# ROHM_102022.net
KiCad netlist of a schematic drawn in EAGLE
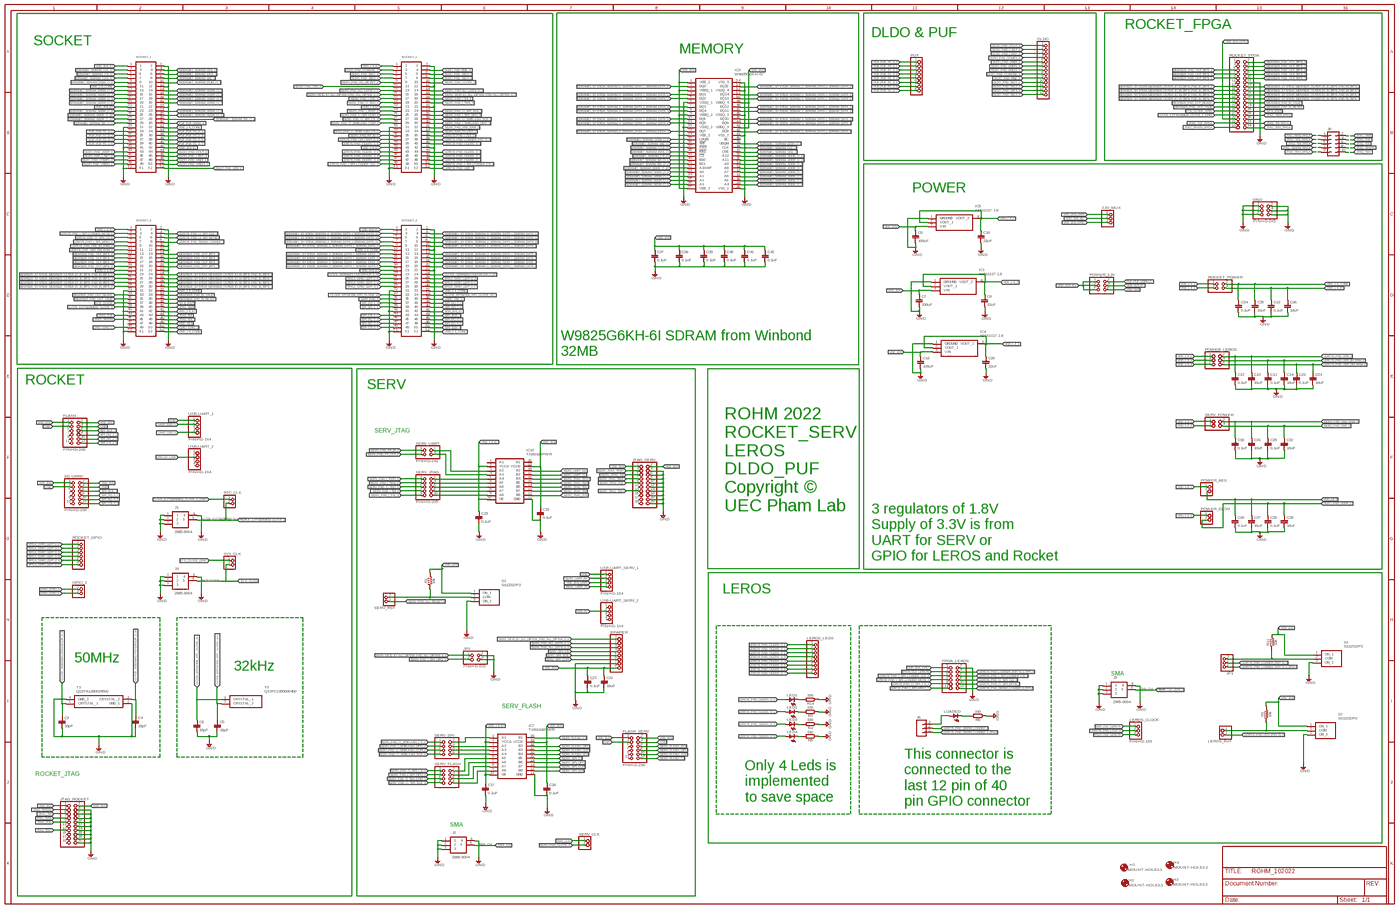
[diagram p0: schematic, sheet 1, overview]
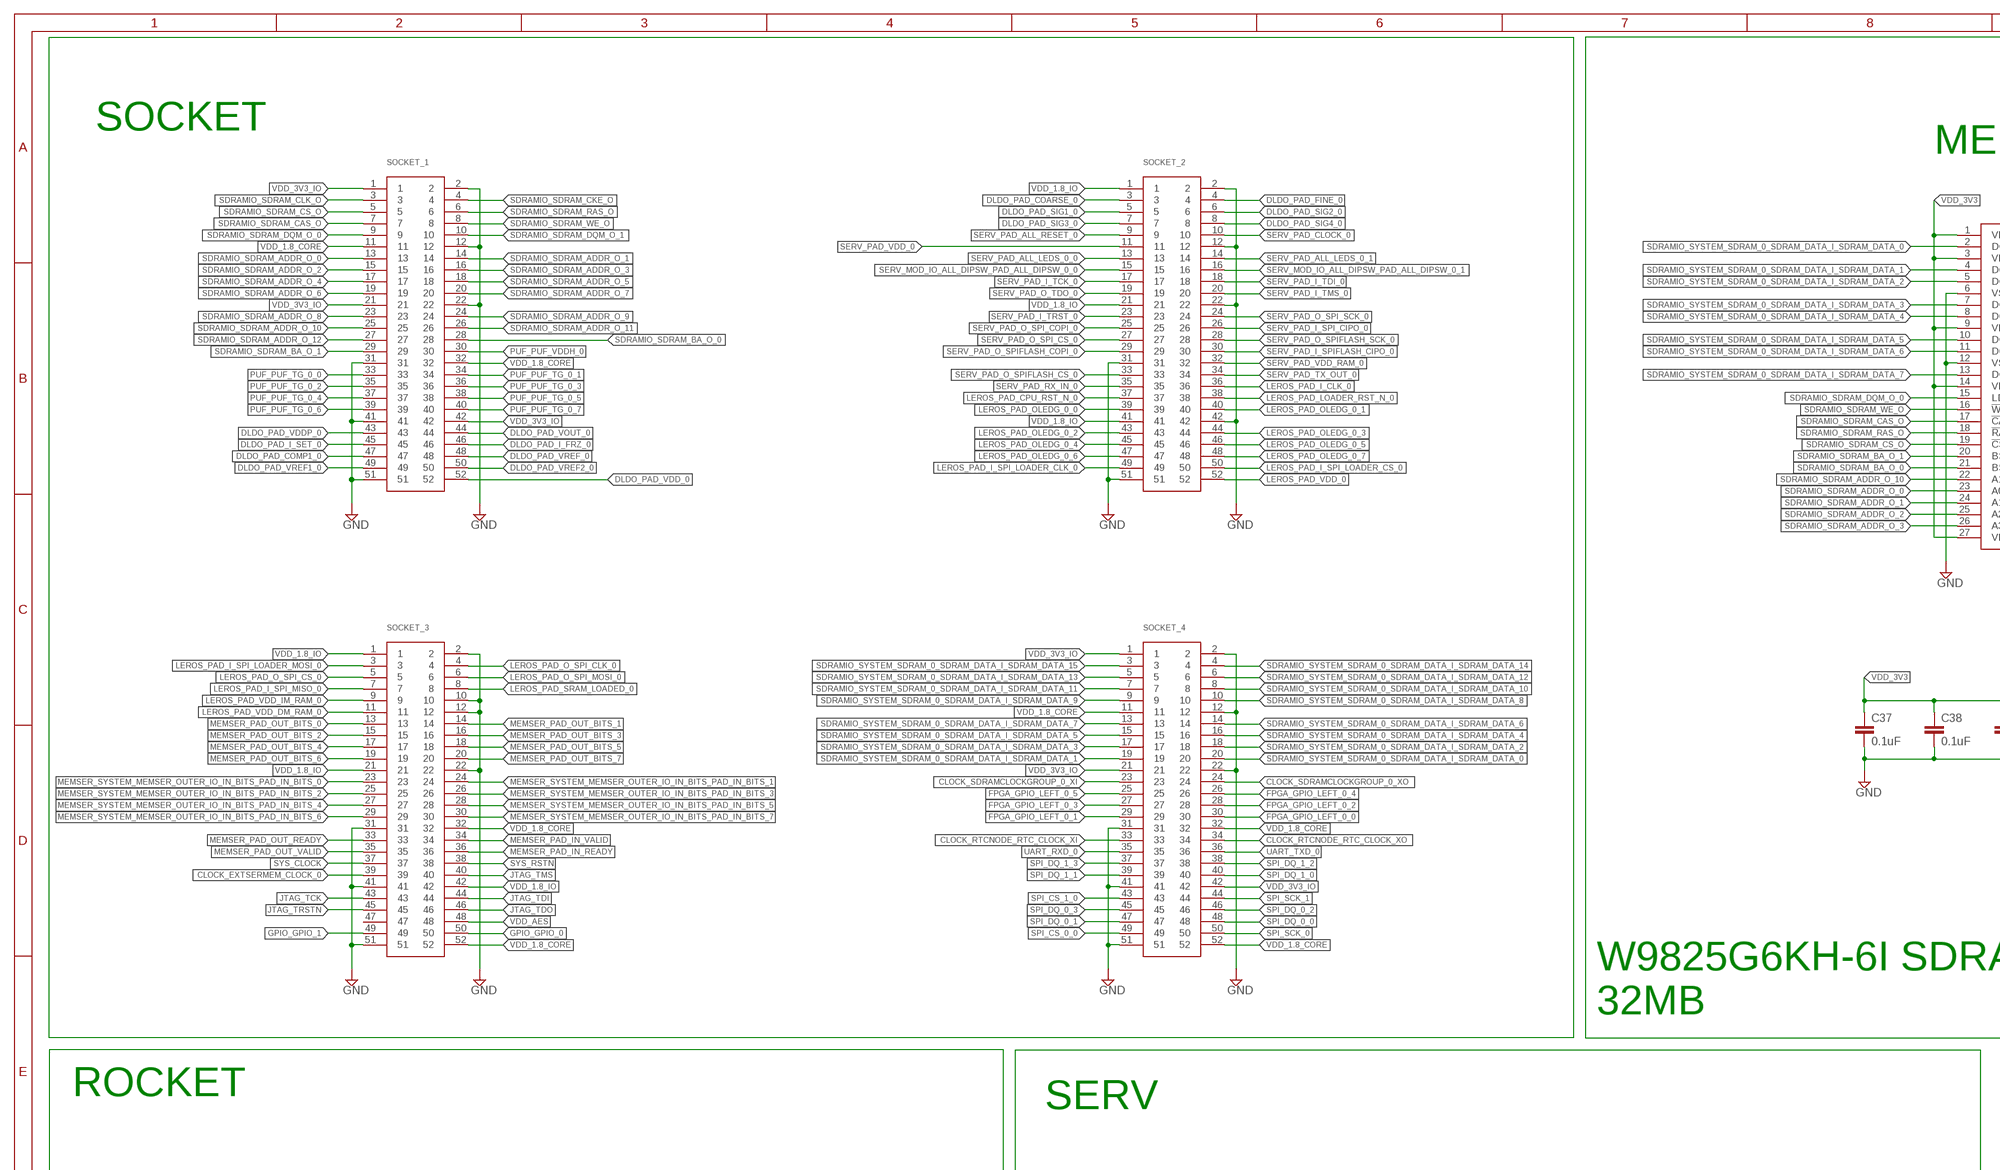
[diagram p1: schematic, sheet 1, part 1 of 4]
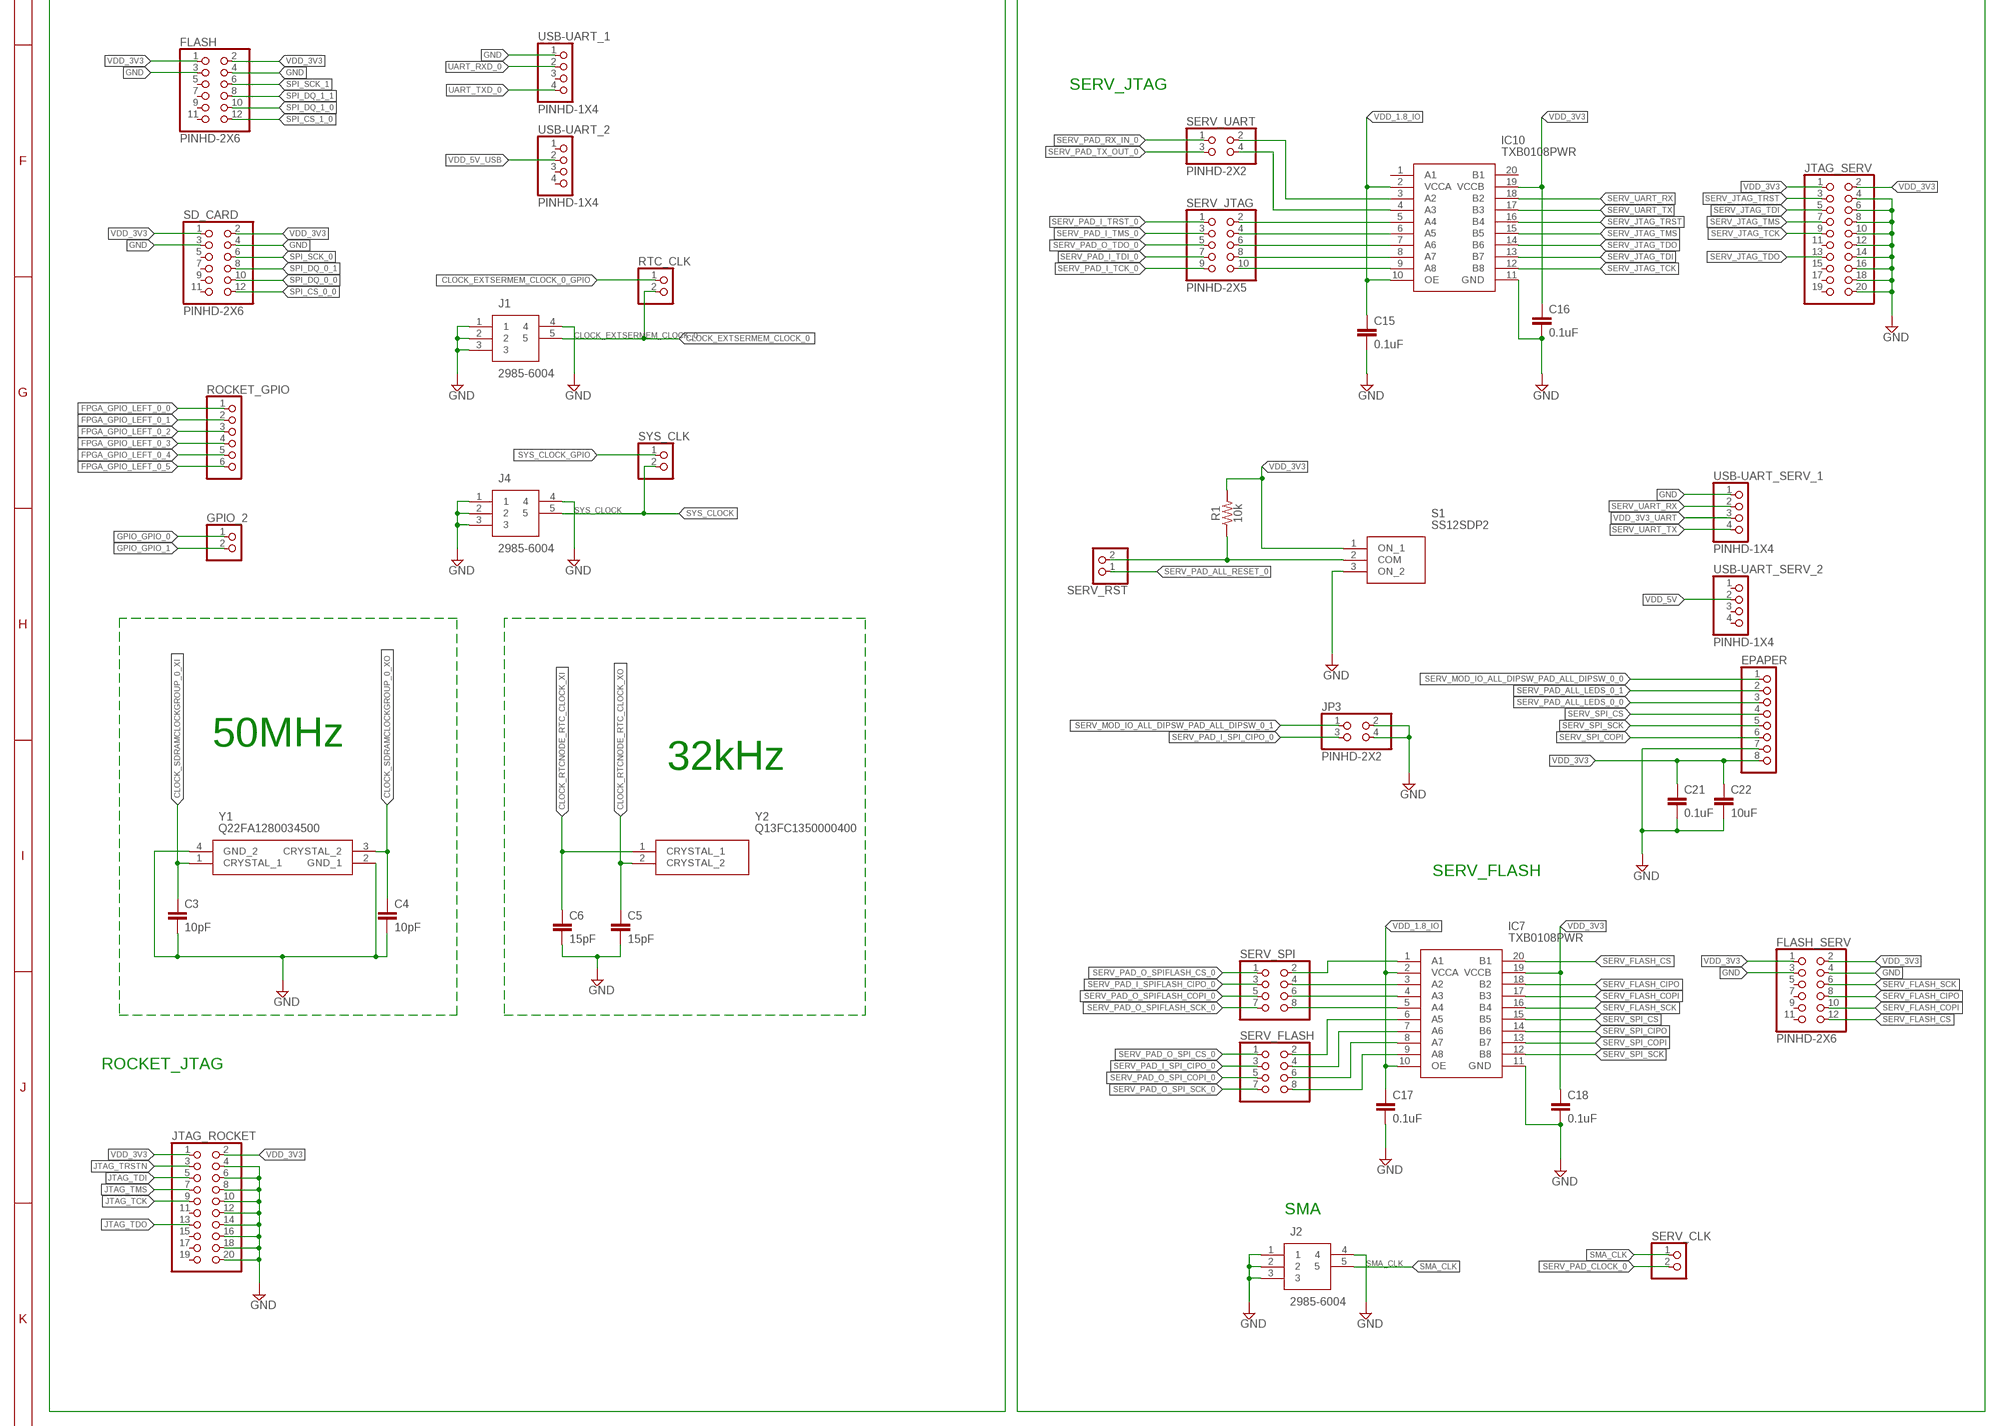
[diagram p2: schematic, sheet 1, part 2 of 4]
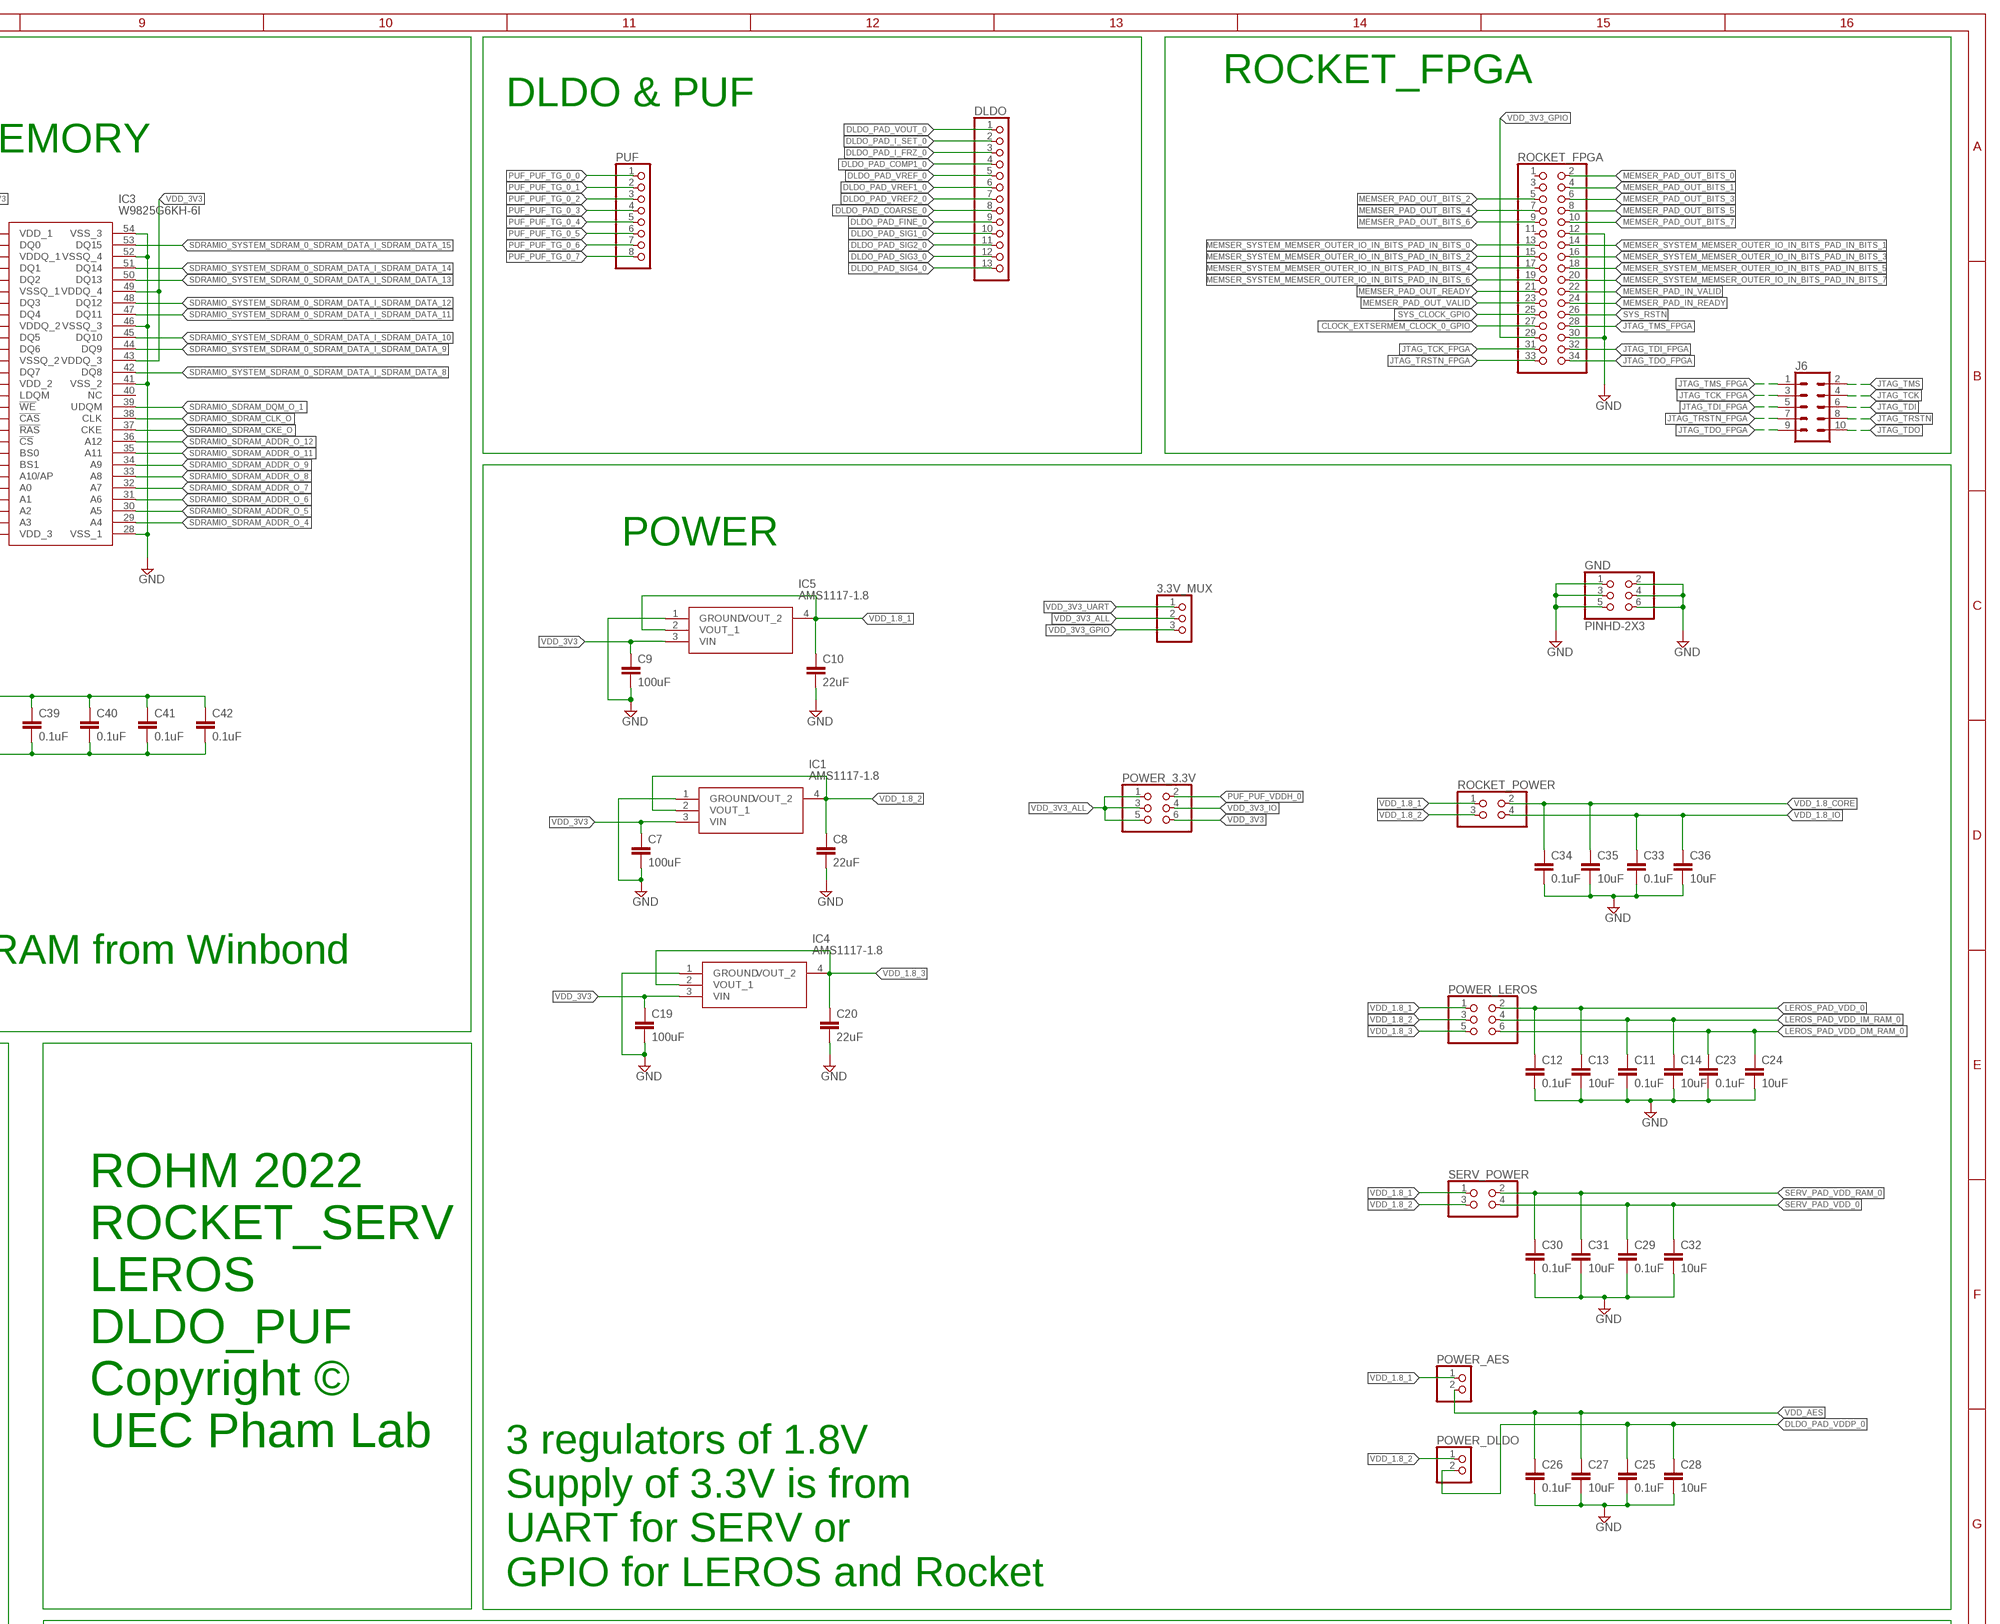
[diagram p3: schematic, sheet 1, part 3 of 4]
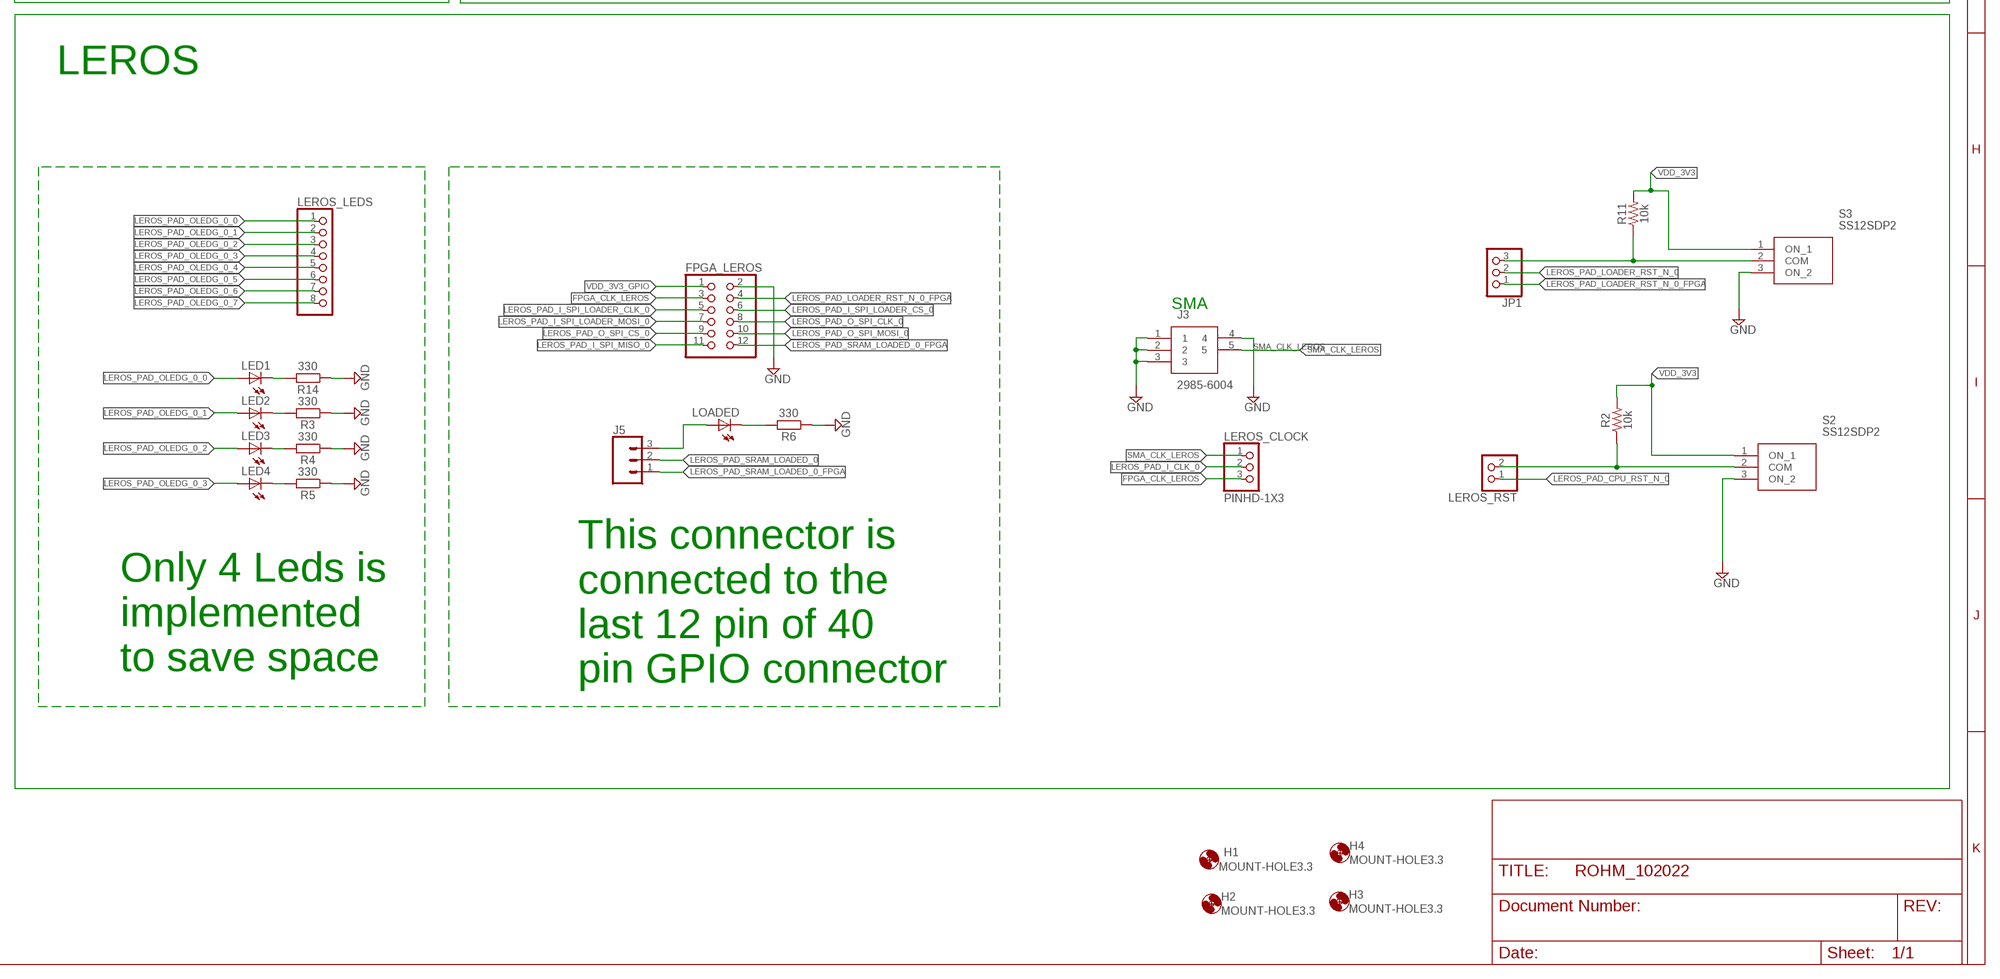
[diagram p4: schematic, sheet 1, part 4 of 4]

(export (version "E")
  (design (tool "Eeschema 10.0.6"))
  (components
    (comp (ref "3.3V_MUX")
      (value "PINHD-1X3")
      (footprint "eagle-import:1X03")
      (libsource (lib "eagle-import") (part "pinhead_325_PINHD-1X3"))
    )
    (comp (ref "C3")
      (value "10pF")
      (footprint "eagle-import:1206")
      (libsource (lib "eagle-import") (part "1.0UF-1206-50V-10%"))
    )
    (comp (ref "C4")
      (value "10pF")
      (footprint "eagle-import:1206")
      (libsource (lib "eagle-import") (part "1.0UF-1206-50V-10%"))
    )
    (comp (ref "C5")
      (value "15pF")
      (footprint "eagle-import:1206")
      (libsource (lib "eagle-import") (part "1.0UF-1206-50V-10%"))
    )
    (comp (ref "C6")
      (value "15pF")
      (footprint "eagle-import:1206")
      (libsource (lib "eagle-import") (part "1.0UF-1206-50V-10%"))
    )
    (comp (ref "C7")
      (value "100uF")
      (footprint "eagle-import:1206")
      (libsource (lib "eagle-import") (part "1.0UF-1206-50V-10%"))
    )
    (comp (ref "C8")
      (value "22uF")
      (footprint "eagle-import:1206")
      (libsource (lib "eagle-import") (part "1.0UF-1206-50V-10%"))
    )
    (comp (ref "C9")
      (value "100uF")
      (footprint "eagle-import:1206")
      (libsource (lib "eagle-import") (part "1.0UF-1206-50V-10%"))
    )
    (comp (ref "C10")
      (value "22uF")
      (footprint "eagle-import:1206")
      (libsource (lib "eagle-import") (part "1.0UF-1206-50V-10%"))
    )
    (comp (ref "C11")
      (value "0.1uF")
      (footprint "eagle-import:1206")
      (libsource (lib "eagle-import") (part "1.0UF-1206-50V-10%"))
    )
    (comp (ref "C12")
      (value "0.1uF")
      (footprint "eagle-import:1206")
      (libsource (lib "eagle-import") (part "1.0UF-1206-50V-10%"))
    )
    (comp (ref "C13")
      (value "10uF")
      (footprint "eagle-import:1206")
      (libsource (lib "eagle-import") (part "1.0UF-1206-50V-10%"))
    )
    (comp (ref "C14")
      (value "10uF")
      (footprint "eagle-import:1206")
      (libsource (lib "eagle-import") (part "1.0UF-1206-50V-10%"))
    )
    (comp (ref "C15")
      (value "0.1uF")
      (footprint "eagle-import:1206")
      (libsource (lib "eagle-import") (part "10UF-1206-6.3V-20%"))
    )
    (comp (ref "C16")
      (value "0.1uF")
      (footprint "eagle-import:1206")
      (libsource (lib "eagle-import") (part "10UF-1206-6.3V-20%"))
    )
    (comp (ref "C17")
      (value "0.1uF")
      (footprint "eagle-import:1206")
      (libsource (lib "eagle-import") (part "10UF-1206-6.3V-20%"))
    )
    (comp (ref "C18")
      (value "0.1uF")
      (footprint "eagle-import:1206")
      (libsource (lib "eagle-import") (part "10UF-1206-6.3V-20%"))
    )
    (comp (ref "C19")
      (value "100uF")
      (footprint "eagle-import:1206")
      (libsource (lib "eagle-import") (part "1.0UF-1206-50V-10%"))
    )
    (comp (ref "C20")
      (value "22uF")
      (footprint "eagle-import:1206")
      (libsource (lib "eagle-import") (part "1.0UF-1206-50V-10%"))
    )
    (comp (ref "C21")
      (value "0.1uF")
      (footprint "eagle-import:1206")
      (libsource (lib "eagle-import") (part "10UF-1206-6.3V-20%"))
    )
    (comp (ref "C22")
      (value "10uF")
      (footprint "eagle-import:1206")
      (libsource (lib "eagle-import") (part "10UF-1206-6.3V-20%"))
    )
    (comp (ref "C23")
      (value "0.1uF")
      (footprint "eagle-import:1206")
      (libsource (lib "eagle-import") (part "1.0UF-1206-50V-10%"))
    )
    (comp (ref "C24")
      (value "10uF")
      (footprint "eagle-import:1206")
      (libsource (lib "eagle-import") (part "1.0UF-1206-50V-10%"))
    )
    (comp (ref "C25")
      (value "0.1uF")
      (footprint "eagle-import:1206")
      (libsource (lib "eagle-import") (part "1.0UF-1206-50V-10%"))
    )
    (comp (ref "C26")
      (value "0.1uF")
      (footprint "eagle-import:1206")
      (libsource (lib "eagle-import") (part "1.0UF-1206-50V-10%"))
    )
    (comp (ref "C27")
      (value "10uF")
      (footprint "eagle-import:1206")
      (libsource (lib "eagle-import") (part "1.0UF-1206-50V-10%"))
    )
    (comp (ref "C28")
      (value "10uF")
      (footprint "eagle-import:1206")
      (libsource (lib "eagle-import") (part "1.0UF-1206-50V-10%"))
    )
    (comp (ref "C29")
      (value "0.1uF")
      (footprint "eagle-import:1206")
      (libsource (lib "eagle-import") (part "1.0UF-1206-50V-10%"))
    )
    (comp (ref "C30")
      (value "0.1uF")
      (footprint "eagle-import:1206")
      (libsource (lib "eagle-import") (part "1.0UF-1206-50V-10%"))
    )
    (comp (ref "C31")
      (value "10uF")
      (footprint "eagle-import:1206")
      (libsource (lib "eagle-import") (part "1.0UF-1206-50V-10%"))
    )
    (comp (ref "C32")
      (value "10uF")
      (footprint "eagle-import:1206")
      (libsource (lib "eagle-import") (part "1.0UF-1206-50V-10%"))
    )
    (comp (ref "C33")
      (value "0.1uF")
      (footprint "eagle-import:1206")
      (libsource (lib "eagle-import") (part "1.0UF-1206-50V-10%"))
    )
    (comp (ref "C34")
      (value "0.1uF")
      (footprint "eagle-import:1206")
      (libsource (lib "eagle-import") (part "1.0UF-1206-50V-10%"))
    )
    (comp (ref "C35")
      (value "10uF")
      (footprint "eagle-import:1206")
      (libsource (lib "eagle-import") (part "1.0UF-1206-50V-10%"))
    )
    (comp (ref "C36")
      (value "10uF")
      (footprint "eagle-import:1206")
      (libsource (lib "eagle-import") (part "1.0UF-1206-50V-10%"))
    )
    (comp (ref "C37")
      (value "0.1uF")
      (footprint "eagle-import:1206")
      (libsource (lib "eagle-import") (part "10UF-1206-6.3V-20%"))
    )
    (comp (ref "C38")
      (value "0.1uF")
      (footprint "eagle-import:1206")
      (libsource (lib "eagle-import") (part "10UF-1206-6.3V-20%"))
    )
    (comp (ref "C39")
      (value "0.1uF")
      (footprint "eagle-import:1206")
      (libsource (lib "eagle-import") (part "10UF-1206-6.3V-20%"))
    )
    (comp (ref "C40")
      (value "0.1uF")
      (footprint "eagle-import:1206")
      (libsource (lib "eagle-import") (part "10UF-1206-6.3V-20%"))
    )
    (comp (ref "C41")
      (value "0.1uF")
      (footprint "eagle-import:1206")
      (libsource (lib "eagle-import") (part "10UF-1206-6.3V-20%"))
    )
    (comp (ref "C42")
      (value "0.1uF")
      (footprint "eagle-import:1206")
      (libsource (lib "eagle-import") (part "10UF-1206-6.3V-20%"))
    )
    (comp (ref "DLDO")
      (value "PINHD-1X13")
      (footprint "eagle-import:1X13")
      (libsource (lib "eagle-import") (part "PINHD-1X13"))
    )
    (comp (ref "EPAPER")
      (value "PINHD-1X8")
      (footprint "eagle-import:1X08")
      (libsource (lib "eagle-import") (part "PINHD-1X8"))
    )
    (comp (ref "FLASH")
      (value "PINHD-2X6")
      (footprint "eagle-import:2X06")
      (libsource (lib "eagle-import") (part "PINHD-2X6"))
    )
    (comp (ref "FLASH_SERV")
      (value "PINHD-2X6")
      (footprint "eagle-import:2X06")
      (libsource (lib "eagle-import") (part "PINHD-2X6"))
    )
    (comp (ref "FPGA_LEROS")
      (value "PINHD-2X6")
      (footprint "eagle-import:2X06")
      (libsource (lib "eagle-import") (part "pinhead_325_PINHD-2X6"))
    )
    (comp (ref "GND")
      (value "PINHD-2X3")
      (footprint "eagle-import:2X03")
      (libsource (lib "eagle-import") (part "PINHD-2X3"))
    )
    (comp (ref "GPIO_2")
      (value "PINHD-1X2")
      (footprint "eagle-import:1X02")
      (libsource (lib "eagle-import") (part "PINHD-1X2"))
    )
    (comp (ref "H1")
      (value "MOUNT-HOLE3.3")
      (footprint "eagle-import:3,3")
      (libsource (lib "eagle-import") (part "MOUNT-HOLE3.3"))
    )
    (comp (ref "H2")
      (value "MOUNT-HOLE3.3")
      (footprint "eagle-import:3,3")
      (libsource (lib "eagle-import") (part "MOUNT-HOLE3.3"))
    )
    (comp (ref "H3")
      (value "MOUNT-HOLE3.3")
      (footprint "eagle-import:3,3")
      (libsource (lib "eagle-import") (part "MOUNT-HOLE3.3"))
    )
    (comp (ref "H4")
      (value "MOUNT-HOLE3.3")
      (footprint "eagle-import:3,3")
      (libsource (lib "eagle-import") (part "MOUNT-HOLE3.3"))
    )
    (comp (ref "IC1")
      (value "AMS1117-1.8")
      (footprint "eagle-import:SOT229P700X180-4N")
      (fields (field (name "MANUFACTURER_PART_NUMBER") "AMS1117"))
      (libsource (lib "eagle-import") (part "AMS1117"))
    )
    (comp (ref "IC3")
      (value "W9825G6KH-6I")
      (footprint "eagle-import:SOP80P1176X120-54N")
      (fields (field (name "MOUSER_PART_NUMBER") "454-W9825G6KH-6I"))
      (libsource (lib "eagle-import") (part "W9825G6KH-6I"))
    )
    (comp (ref "IC4")
      (value "AMS1117-1.8")
      (footprint "eagle-import:SOT229P700X180-4N")
      (fields (field (name "MANUFACTURER_PART_NUMBER") "AMS1117"))
      (libsource (lib "eagle-import") (part "AMS1117"))
    )
    (comp (ref "IC5")
      (value "AMS1117-1.8")
      (footprint "eagle-import:SOT229P700X180-4N")
      (fields (field (name "MANUFACTURER_PART_NUMBER") "AMS1117"))
      (libsource (lib "eagle-import") (part "AMS1117"))
    )
    (comp (ref "IC7")
      (value "TXB0108PWR")
      (footprint "eagle-import:SOP65P640X120-20N")
      (fields (field (name "MOUSER_PART_NUMBER") "595-TXB0108PWR"))
      (libsource (lib "eagle-import") (part "TXB0108PWR"))
    )
    (comp (ref "IC10")
      (value "TXB0108PWR")
      (footprint "eagle-import:SOP65P640X120-20N")
      (fields (field (name "MOUSER_PART_NUMBER") "595-TXB0108PWR"))
      (libsource (lib "eagle-import") (part "TXB0108PWR"))
    )
    (comp (ref "J1")
      (value "2985-6004")
      (footprint "eagle-import:29856004")
      (fields (field (name "MOUSER_PART_NUMBER") "523-2985-6004"))
      (libsource (lib "eagle-import") (part "2985-6004"))
    )
    (comp (ref "J2")
      (value "2985-6004")
      (footprint "eagle-import:29856004")
      (fields (field (name "MOUSER_PART_NUMBER") "523-2985-6004"))
      (libsource (lib "eagle-import") (part "2985-6004"))
    )
    (comp (ref "J3")
      (value "2985-6004")
      (footprint "eagle-import:29856004")
      (fields (field (name "MOUSER_PART_NUMBER") "523-2985-6004"))
      (libsource (lib "eagle-import") (part "2985-6004"))
    )
    (comp (ref "J4")
      (value "2985-6004")
      (footprint "eagle-import:29856004")
      (fields (field (name "MOUSER_PART_NUMBER") "523-2985-6004"))
      (libsource (lib "eagle-import") (part "2985-6004"))
    )
    (comp (ref "J5")
      (value "CONN_03")
      (footprint "eagle-import:1X03")
      (libsource (lib "eagle-import") (part "CONN_03"))
    )
    (comp (ref "J6")
      (value "CONN_05X2PTH")
      (footprint "eagle-import:2X5")
      (libsource (lib "eagle-import") (part "CONN_05X2PTH"))
    )
    (comp (ref "JP1")
      (value "PINHD-1X3")
      (footprint "eagle-import:1X03")
      (libsource (lib "eagle-import") (part "pinhead_325_PINHD-1X3"))
    )
    (comp (ref "JP3")
      (value "PINHD-2X2")
      (footprint "eagle-import:2X02")
      (libsource (lib "eagle-import") (part "PINHD-2X2"))
    )
    (comp (ref "JTAG_ROCKET")
      (value "PINHD-2X10")
      (footprint "eagle-import:2X10")
      (libsource (lib "eagle-import") (part "PINHD-2X10"))
    )
    (comp (ref "JTAG_SERV")
      (value "PINHD-2X10")
      (footprint "eagle-import:2X10")
      (libsource (lib "eagle-import") (part "PINHD-2X10"))
    )
    (comp (ref "LED1")
      (value "LEDCHIPLED_0805")
      (footprint "eagle-import:CHIPLED_0805")
      (libsource (lib "eagle-import") (part "LEDCHIPLED_0805"))
    )
    (comp (ref "LED2")
      (value "LEDCHIPLED_0805")
      (footprint "eagle-import:CHIPLED_0805")
      (libsource (lib "eagle-import") (part "LEDCHIPLED_0805"))
    )
    (comp (ref "LED3")
      (value "LEDCHIPLED_0805")
      (footprint "eagle-import:CHIPLED_0805")
      (libsource (lib "eagle-import") (part "LEDCHIPLED_0805"))
    )
    (comp (ref "LED4")
      (value "LEDCHIPLED_0805")
      (footprint "eagle-import:CHIPLED_0805")
      (libsource (lib "eagle-import") (part "LEDCHIPLED_0805"))
    )
    (comp (ref "LEROS_CLOCK")
      (value "PINHD-1X3")
      (footprint "eagle-import:1X03")
      (libsource (lib "eagle-import") (part "PINHD-1X3"))
    )
    (comp (ref "LEROS_LEDS")
      (value "PINHD-1X8")
      (footprint "eagle-import:1X08")
      (libsource (lib "eagle-import") (part "PINHD-1X8"))
    )
    (comp (ref "LEROS_RST")
      (value "PINHD-1X2")
      (footprint "eagle-import:1X02")
      (libsource (lib "eagle-import") (part "PINHD-1X2"))
    )
    (comp (ref "LOADED")
      (value "LEDCHIPLED_0805")
      (footprint "eagle-import:CHIPLED_0805")
      (libsource (lib "eagle-import") (part "LEDCHIPLED_0805"))
    )
    (comp (ref "POWER_3.3V")
      (value "PINHD-2X3")
      (footprint "eagle-import:2X03")
      (libsource (lib "eagle-import") (part "pinhead_325_PINHD-2X3"))
    )
    (comp (ref "POWER_AES")
      (value "PINHD-1X2")
      (footprint "eagle-import:1X02")
      (libsource (lib "eagle-import") (part "PINHD-1X2"))
    )
    (comp (ref "POWER_DLDO")
      (value "PINHD-1X2")
      (footprint "eagle-import:1X02")
      (libsource (lib "eagle-import") (part "PINHD-1X2"))
    )
    (comp (ref "POWER_LEROS")
      (value "PINHD-2X3")
      (footprint "eagle-import:2X03")
      (libsource (lib "eagle-import") (part "pinhead_325_PINHD-2X3"))
    )
    (comp (ref "PUF")
      (value "PINHD-1X8")
      (footprint "eagle-import:1X08")
      (libsource (lib "eagle-import") (part "PINHD-1X8"))
    )
    (comp (ref "R1")
      (value "10k")
      (footprint "eagle-import:1206")
      (libsource (lib "eagle-import") (part "10OHM-1206-1/4W-1%"))
    )
    (comp (ref "R2")
      (value "10k")
      (footprint "eagle-import:1206")
      (libsource (lib "eagle-import") (part "10OHM-1206-1/4W-1%"))
    )
    (comp (ref "R3")
      (value "330")
      (footprint "eagle-import:RESC3216X70")
      (libsource (lib "eagle-import") (part "RCHIP-1206(3216-METRIC)_"))
    )
    (comp (ref "R4")
      (value "330")
      (footprint "eagle-import:RESC3216X70")
      (libsource (lib "eagle-import") (part "RCHIP-1206(3216-METRIC)_"))
    )
    (comp (ref "R5")
      (value "330")
      (footprint "eagle-import:RESC3216X70")
      (libsource (lib "eagle-import") (part "RCHIP-1206(3216-METRIC)_"))
    )
    (comp (ref "R6")
      (value "330")
      (footprint "eagle-import:RESC3216X70")
      (libsource (lib "eagle-import") (part "RCHIP-1206(3216-METRIC)_"))
    )
    (comp (ref "R11")
      (value "10k")
      (footprint "eagle-import:1206")
      (libsource (lib "eagle-import") (part "10OHM-1206-1/4W-1%"))
    )
    (comp (ref "R14")
      (value "330")
      (footprint "eagle-import:RESC3216X70")
      (libsource (lib "eagle-import") (part "RCHIP-1206(3216-METRIC)_"))
    )
    (comp (ref "ROCKET_FPGA")
      (value "PINHD-2X17")
      (footprint "eagle-import:2X17")
      (libsource (lib "eagle-import") (part "PINHD-2X17"))
    )
    (comp (ref "ROCKET_GPIO")
      (value "PINHD-1X6")
      (footprint "eagle-import:1X06")
      (libsource (lib "eagle-import") (part "PINHD-1X6"))
    )
    (comp (ref "ROCKET_POWER")
      (value "PINHD-2X2")
      (footprint "eagle-import:2X02")
      (libsource (lib "eagle-import") (part "pinhead_325_PINHD-2X2"))
    )
    (comp (ref "RTC_CLK")
      (value "PINHD-1X2")
      (footprint "eagle-import:1X02")
      (libsource (lib "eagle-import") (part "PINHD-1X2"))
    )
    (comp (ref "S1")
      (value "SS12SDP2")
      (footprint "eagle-import:SS12SDP2")
      (fields (field (name "MOUSER_PART_NUMBER") "633-SS12SDP2"))
      (libsource (lib "eagle-import") (part "SS12SDP2"))
    )
    (comp (ref "S2")
      (value "SS12SDP2")
      (footprint "eagle-import:SS12SDP2")
      (fields (field (name "MOUSER_PART_NUMBER") "633-SS12SDP2"))
      (libsource (lib "eagle-import") (part "SS12SDP2"))
    )
    (comp (ref "S3")
      (value "SS12SDP2")
      (footprint "eagle-import:SS12SDP2")
      (fields (field (name "MOUSER_PART_NUMBER") "633-SS12SDP2"))
      (libsource (lib "eagle-import") (part "SS12SDP2"))
    )
    (comp (ref "SD_CARD")
      (value "PINHD-2X6")
      (footprint "eagle-import:2X06")
      (libsource (lib "eagle-import") (part "PINHD-2X6"))
    )
    (comp (ref "SERV_CLK")
      (value "PINHD-1X2")
      (footprint "eagle-import:1X02")
      (libsource (lib "eagle-import") (part "PINHD-1X2"))
    )
    (comp (ref "SERV_FLASH")
      (value "PINHD-2X4")
      (footprint "eagle-import:2X04")
      (libsource (lib "eagle-import") (part "PINHD-2X4"))
    )
    (comp (ref "SERV_JTAG")
      (value "PINHD-2X5")
      (footprint "eagle-import:2X05")
      (libsource (lib "eagle-import") (part "PINHD-2X5"))
    )
    (comp (ref "SERV_POWER")
      (value "PINHD-2X2")
      (footprint "eagle-import:2X02")
      (libsource (lib "eagle-import") (part "pinhead_325_PINHD-2X2"))
    )
    (comp (ref "SERV_RST")
      (value "PINHD-1X2")
      (footprint "eagle-import:1X02")
      (libsource (lib "eagle-import") (part "PINHD-1X2"))
    )
    (comp (ref "SERV_SPI")
      (value "PINHD-2X4")
      (footprint "eagle-import:2X04")
      (libsource (lib "eagle-import") (part "PINHD-2X4"))
    )
    (comp (ref "SERV_UART")
      (value "PINHD-2X2")
      (footprint "eagle-import:2X02")
      (libsource (lib "eagle-import") (part "PINHD-2X2"))
    )
    (comp (ref "SOCKET_1")
      (value "2X26_HEADER")
      (footprint "eagle-import:2X26_HEADER")
      (libsource (lib "eagle-import") (part "2X26_HEADER"))
    )
    (comp (ref "SOCKET_2")
      (value "2X26_HEADER")
      (footprint "eagle-import:2X26_HEADER")
      (libsource (lib "eagle-import") (part "2X26_HEADER"))
    )
    (comp (ref "SOCKET_3")
      (value "2X26_HEADER")
      (footprint "eagle-import:2X26_HEADER")
      (libsource (lib "eagle-import") (part "2X26_HEADER"))
    )
    (comp (ref "SOCKET_4")
      (value "2X26_HEADER")
      (footprint "eagle-import:2X26_HEADER")
      (libsource (lib "eagle-import") (part "2X26_HEADER"))
    )
    (comp (ref "SYS_CLK")
      (value "PINHD-1X2")
      (footprint "eagle-import:1X02")
      (libsource (lib "eagle-import") (part "PINHD-1X2"))
    )
    (comp (ref "USB-UART_1")
      (value "PINHD-1X4")
      (footprint "eagle-import:1X04")
      (libsource (lib "eagle-import") (part "PINHD-1X4"))
    )
    (comp (ref "USB-UART_2")
      (value "PINHD-1X4")
      (footprint "eagle-import:1X04")
      (libsource (lib "eagle-import") (part "PINHD-1X4"))
    )
    (comp (ref "USB-UART_SERV_1")
      (value "PINHD-1X4")
      (footprint "eagle-import:1X04")
      (libsource (lib "eagle-import") (part "PINHD-1X4"))
    )
    (comp (ref "USB-UART_SERV_2")
      (value "PINHD-1X4")
      (footprint "eagle-import:1X04")
      (libsource (lib "eagle-import") (part "PINHD-1X4"))
    )
    (comp (ref "Y1")
      (value "Q22FA1280034500")
      (footprint "eagle-import:Q22FA1280034500")
      (libsource (lib "eagle-import") (part "Q22FA1280034500"))
    )
    (comp (ref "Y2")
      (value "Q13FC1350000400")
      (footprint "eagle-import:Q13FC1350000400")
      (libsource (lib "eagle-import") (part "Q13FC1350000400"))
    )
  )
  (nets
    (net (code "1") (name "CLOCK_EXTSERMEM_CLOCK_0") (class "Default")
      (node (ref "J1") (pin "5") (pinfunction "5_5") (pintype "bidirectional"))
      (node (ref "RTC_CLK") (pin "2") (pinfunction "2_2") (pintype "passive"))
      (node (ref "SOCKET_3") (pin "39") (pinfunction "39_39") (pintype "bidirectional"))
    )
    (net (code "2") (name "CLOCK_EXTSERMEM_CLOCK_0_GPIO") (class "Default")
      (node (ref "ROCKET_FPGA") (pin "27") (pinfunction "27_27") (pintype "passive"))
      (node (ref "RTC_CLK") (pin "1") (pinfunction "1_1") (pintype "passive"))
    )
    (net (code "3") (name "CLOCK_RTCNODE_RTC_CLOCK_XI") (class "Default")
      (node (ref "C6") (pin "1") (pinfunction "1_1") (pintype "passive"))
      (node (ref "SOCKET_4") (pin "33") (pinfunction "33_33") (pintype "bidirectional"))
      (node (ref "Y2") (pin "1") (pinfunction "CRYSTAL_1_1") (pintype "bidirectional"))
    )
    (net (code "4") (name "CLOCK_RTCNODE_RTC_CLOCK_XO") (class "Default")
      (node (ref "C5") (pin "1") (pinfunction "1_1") (pintype "passive"))
      (node (ref "SOCKET_4") (pin "34") (pinfunction "34_34") (pintype "bidirectional"))
      (node (ref "Y2") (pin "2") (pinfunction "CRYSTAL_2_2") (pintype "bidirectional"))
    )
    (net (code "5") (name "CLOCK_SDRAMCLOCKGROUP_0_XI") (class "Default")
      (node (ref "C3") (pin "1") (pinfunction "1_1") (pintype "passive"))
      (node (ref "SOCKET_4") (pin "23") (pinfunction "23_23") (pintype "bidirectional"))
      (node (ref "Y1") (pin "1") (pinfunction "CRYSTAL_1_1") (pintype "bidirectional"))
    )
    (net (code "6") (name "CLOCK_SDRAMCLOCKGROUP_0_XO") (class "Default")
      (node (ref "C4") (pin "1") (pinfunction "1_1") (pintype "passive"))
      (node (ref "SOCKET_4") (pin "24") (pinfunction "24_24") (pintype "bidirectional"))
      (node (ref "Y1") (pin "3") (pinfunction "CRYSTAL_2_3") (pintype "bidirectional"))
    )
    (net (code "7") (name "DLDO_PAD_COARSE_0") (class "Default")
      (node (ref "DLDO") (pin "8") (pinfunction "8_8") (pintype "passive"))
      (node (ref "SOCKET_2") (pin "3") (pinfunction "3_3") (pintype "bidirectional"))
    )
    (net (code "8") (name "DLDO_PAD_COMP1_0") (class "Default")
      (node (ref "DLDO") (pin "4") (pinfunction "4_4") (pintype "passive"))
      (node (ref "SOCKET_1") (pin "47") (pinfunction "47_47") (pintype "bidirectional"))
    )
    (net (code "9") (name "DLDO_PAD_FINE_0") (class "Default")
      (node (ref "DLDO") (pin "9") (pinfunction "9_9") (pintype "passive"))
      (node (ref "SOCKET_2") (pin "4") (pinfunction "4_4") (pintype "bidirectional"))
    )
    (net (code "10") (name "DLDO_PAD_I_FRZ_0") (class "Default")
      (node (ref "DLDO") (pin "3") (pinfunction "3_3") (pintype "passive"))
      (node (ref "SOCKET_1") (pin "46") (pinfunction "46_46") (pintype "bidirectional"))
    )
    (net (code "11") (name "DLDO_PAD_I_SET_0") (class "Default")
      (node (ref "DLDO") (pin "2") (pinfunction "2_2") (pintype "passive"))
      (node (ref "SOCKET_1") (pin "45") (pinfunction "45_45") (pintype "bidirectional"))
    )
    (net (code "12") (name "DLDO_PAD_SIG1_0") (class "Default")
      (node (ref "DLDO") (pin "10") (pinfunction "10_10") (pintype "passive"))
      (node (ref "SOCKET_2") (pin "5") (pinfunction "5_5") (pintype "bidirectional"))
    )
    (net (code "13") (name "DLDO_PAD_SIG2_0") (class "Default")
      (node (ref "DLDO") (pin "11") (pinfunction "11_11") (pintype "passive"))
      (node (ref "SOCKET_2") (pin "6") (pinfunction "6_6") (pintype "bidirectional"))
    )
    (net (code "14") (name "DLDO_PAD_SIG3_0") (class "Default")
      (node (ref "DLDO") (pin "12") (pinfunction "12_12") (pintype "passive"))
      (node (ref "SOCKET_2") (pin "7") (pinfunction "7_7") (pintype "bidirectional"))
    )
    (net (code "15") (name "DLDO_PAD_SIG4_0") (class "Default")
      (node (ref "DLDO") (pin "13") (pinfunction "13_13") (pintype "passive"))
      (node (ref "SOCKET_2") (pin "8") (pinfunction "8_8") (pintype "bidirectional"))
    )
    (net (code "16") (name "DLDO_PAD_VDDP_0") (class "Default")
      (node (ref "C25") (pin "1") (pinfunction "1_1") (pintype "passive"))
      (node (ref "C28") (pin "1") (pinfunction "1_1") (pintype "passive"))
      (node (ref "POWER_DLDO") (pin "2") (pinfunction "2_2") (pintype "passive"))
      (node (ref "SOCKET_1") (pin "43") (pinfunction "43_43") (pintype "bidirectional"))
    )
    (net (code "17") (name "DLDO_PAD_VDD_0") (class "Default")
      (node (ref "SOCKET_1") (pin "52") (pinfunction "52_52") (pintype "bidirectional"))
    )
    (net (code "18") (name "DLDO_PAD_VOUT_0") (class "Default")
      (node (ref "DLDO") (pin "1") (pinfunction "1_1") (pintype "passive"))
      (node (ref "SOCKET_1") (pin "44") (pinfunction "44_44") (pintype "bidirectional"))
    )
    (net (code "19") (name "DLDO_PAD_VREF1_0") (class "Default")
      (node (ref "DLDO") (pin "6") (pinfunction "6_6") (pintype "passive"))
      (node (ref "SOCKET_1") (pin "49") (pinfunction "49_49") (pintype "bidirectional"))
    )
    (net (code "20") (name "DLDO_PAD_VREF2_0") (class "Default")
      (node (ref "DLDO") (pin "7") (pinfunction "7_7") (pintype "passive"))
      (node (ref "SOCKET_1") (pin "50") (pinfunction "50_50") (pintype "bidirectional"))
    )
    (net (code "21") (name "DLDO_PAD_VREF_0") (class "Default")
      (node (ref "DLDO") (pin "5") (pinfunction "5_5") (pintype "passive"))
      (node (ref "SOCKET_1") (pin "48") (pinfunction "48_48") (pintype "bidirectional"))
    )
    (net (code "22") (name "FPGA_CLK_LEROS") (class "Default")
      (node (ref "FPGA_LEROS") (pin "3") (pinfunction "3_3") (pintype "passive"))
      (node (ref "LEROS_CLOCK") (pin "3") (pinfunction "3_3") (pintype "passive"))
    )
    (net (code "23") (name "FPGA_GPIO_LEFT_0_0") (class "Default")
      (node (ref "ROCKET_GPIO") (pin "1") (pinfunction "1_1") (pintype "passive"))
      (node (ref "SOCKET_4") (pin "30") (pinfunction "30_30") (pintype "bidirectional"))
    )
    (net (code "24") (name "FPGA_GPIO_LEFT_0_1") (class "Default")
      (node (ref "ROCKET_GPIO") (pin "2") (pinfunction "2_2") (pintype "passive"))
      (node (ref "SOCKET_4") (pin "29") (pinfunction "29_29") (pintype "bidirectional"))
    )
    (net (code "25") (name "FPGA_GPIO_LEFT_0_2") (class "Default")
      (node (ref "ROCKET_GPIO") (pin "3") (pinfunction "3_3") (pintype "passive"))
      (node (ref "SOCKET_4") (pin "28") (pinfunction "28_28") (pintype "bidirectional"))
    )
    (net (code "26") (name "FPGA_GPIO_LEFT_0_3") (class "Default")
      (node (ref "ROCKET_GPIO") (pin "4") (pinfunction "4_4") (pintype "passive"))
      (node (ref "SOCKET_4") (pin "27") (pinfunction "27_27") (pintype "bidirectional"))
    )
    (net (code "27") (name "FPGA_GPIO_LEFT_0_4") (class "Default")
      (node (ref "ROCKET_GPIO") (pin "5") (pinfunction "5_5") (pintype "passive"))
      (node (ref "SOCKET_4") (pin "26") (pinfunction "26_26") (pintype "bidirectional"))
    )
    (net (code "28") (name "FPGA_GPIO_LEFT_0_5") (class "Default")
      (node (ref "ROCKET_GPIO") (pin "6") (pinfunction "6_6") (pintype "passive"))
      (node (ref "SOCKET_4") (pin "25") (pinfunction "25_25") (pintype "bidirectional"))
    )
    (net (code "29") (name "GND") (class "Default")
      (node (ref "C10") (pin "2") (pinfunction "2_2") (pintype "passive"))
      (node (ref "C11") (pin "2") (pinfunction "2_2") (pintype "passive"))
      (node (ref "C12") (pin "2") (pinfunction "2_2") (pintype "passive"))
      (node (ref "C13") (pin "2") (pinfunction "2_2") (pintype "passive"))
      (node (ref "C14") (pin "2") (pinfunction "2_2") (pintype "passive"))
      (node (ref "C15") (pin "2") (pinfunction "2_2") (pintype "passive"))
      (node (ref "C16") (pin "2") (pinfunction "2_2") (pintype "passive"))
      (node (ref "C17") (pin "2") (pinfunction "2_2") (pintype "passive"))
      (node (ref "C18") (pin "2") (pinfunction "2_2") (pintype "passive"))
      (node (ref "C19") (pin "2") (pinfunction "2_2") (pintype "passive"))
      (node (ref "C20") (pin "2") (pinfunction "2_2") (pintype "passive"))
      (node (ref "C21") (pin "2") (pinfunction "2_2") (pintype "passive"))
      (node (ref "C22") (pin "2") (pinfunction "2_2") (pintype "passive"))
      (node (ref "C23") (pin "2") (pinfunction "2_2") (pintype "passive"))
      (node (ref "C24") (pin "2") (pinfunction "2_2") (pintype "passive"))
      (node (ref "C25") (pin "2") (pinfunction "2_2") (pintype "passive"))
      (node (ref "C26") (pin "2") (pinfunction "2_2") (pintype "passive"))
      (node (ref "C27") (pin "2") (pinfunction "2_2") (pintype "passive"))
      (node (ref "C28") (pin "2") (pinfunction "2_2") (pintype "passive"))
      (node (ref "C29") (pin "2") (pinfunction "2_2") (pintype "passive"))
      (node (ref "C3") (pin "2") (pinfunction "2_2") (pintype "passive"))
      (node (ref "C30") (pin "2") (pinfunction "2_2") (pintype "passive"))
      (node (ref "C31") (pin "2") (pinfunction "2_2") (pintype "passive"))
      (node (ref "C32") (pin "2") (pinfunction "2_2") (pintype "passive"))
      (node (ref "C33") (pin "2") (pinfunction "2_2") (pintype "passive"))
      (node (ref "C34") (pin "2") (pinfunction "2_2") (pintype "passive"))
      (node (ref "C35") (pin "2") (pinfunction "2_2") (pintype "passive"))
      (node (ref "C36") (pin "2") (pinfunction "2_2") (pintype "passive"))
      (node (ref "C37") (pin "2") (pinfunction "2_2") (pintype "passive"))
      (node (ref "C38") (pin "2") (pinfunction "2_2") (pintype "passive"))
      (node (ref "C39") (pin "2") (pinfunction "2_2") (pintype "passive"))
      (node (ref "C4") (pin "2") (pinfunction "2_2") (pintype "passive"))
      (node (ref "C40") (pin "2") (pinfunction "2_2") (pintype "passive"))
      (node (ref "C41") (pin "2") (pinfunction "2_2") (pintype "passive"))
      (node (ref "C42") (pin "2") (pinfunction "2_2") (pintype "passive"))
      (node (ref "C5") (pin "2") (pinfunction "2_2") (pintype "passive"))
      (node (ref "C6") (pin "2") (pinfunction "2_2") (pintype "passive"))
      (node (ref "C7") (pin "2") (pinfunction "2_2") (pintype "passive"))
      (node (ref "C8") (pin "2") (pinfunction "2_2") (pintype "passive"))
      (node (ref "C9") (pin "2") (pinfunction "2_2") (pintype "passive"))
      (node (ref "EPAPER") (pin "7") (pinfunction "7_7") (pintype "passive"))
      (node (ref "FLASH") (pin "3") (pinfunction "3_3") (pintype "passive"))
      (node (ref "FLASH") (pin "4") (pinfunction "4_4") (pintype "passive"))
      (node (ref "FLASH_SERV") (pin "3") (pinfunction "3_3") (pintype "passive"))
      (node (ref "FLASH_SERV") (pin "4") (pinfunction "4_4") (pintype "passive"))
      (node (ref "FPGA_LEROS") (pin "2") (pinfunction "2_2") (pintype "passive"))
      (node (ref "GND") (pin "1") (pinfunction "1_1") (pintype "passive"))
      (node (ref "GND") (pin "2") (pinfunction "2_2") (pintype "passive"))
      (node (ref "GND") (pin "3") (pinfunction "3_3") (pintype "passive"))
      (node (ref "GND") (pin "4") (pinfunction "4_4") (pintype "passive"))
      (node (ref "GND") (pin "5") (pinfunction "5_5") (pintype "passive"))
      (node (ref "GND") (pin "6") (pinfunction "6_6") (pintype "passive"))
      (node (ref "IC1") (pin "1") (pinfunction "GROUND_1") (pintype "bidirectional"))
      (node (ref "IC10") (pin "11") (pinfunction "GND_11") (pintype "bidirectional"))
      (node (ref "IC3") (pin "12") (pinfunction "VSSQ_2_12") (pintype "bidirectional"))
      (node (ref "IC3") (pin "28") (pinfunction "VSS_1_28") (pintype "bidirectional"))
      (node (ref "IC3") (pin "41") (pinfunction "VSS_2_41") (pintype "bidirectional"))
      (node (ref "IC3") (pin "46") (pinfunction "VSSQ_3_46") (pintype "bidirectional"))
      (node (ref "IC3") (pin "52") (pinfunction "VSSQ_4_52") (pintype "bidirectional"))
      (node (ref "IC3") (pin "54") (pinfunction "VSS_3_54") (pintype "bidirectional"))
      (node (ref "IC3") (pin "6") (pinfunction "VSSQ_1_6") (pintype "bidirectional"))
      (node (ref "IC4") (pin "1") (pinfunction "GROUND_1") (pintype "bidirectional"))
      (node (ref "IC5") (pin "1") (pinfunction "GROUND_1") (pintype "bidirectional"))
      (node (ref "IC7") (pin "11") (pinfunction "GND_11") (pintype "bidirectional"))
      (node (ref "J1") (pin "1") (pinfunction "1_1") (pintype "bidirectional"))
      (node (ref "J1") (pin "2") (pinfunction "2_2") (pintype "bidirectional"))
      (node (ref "J1") (pin "3") (pinfunction "3_3") (pintype "bidirectional"))
      (node (ref "J1") (pin "4") (pinfunction "4_4") (pintype "bidirectional"))
      (node (ref "J2") (pin "1") (pinfunction "1_1") (pintype "bidirectional"))
      (node (ref "J2") (pin "2") (pinfunction "2_2") (pintype "bidirectional"))
      (node (ref "J2") (pin "3") (pinfunction "3_3") (pintype "bidirectional"))
      (node (ref "J2") (pin "4") (pinfunction "4_4") (pintype "bidirectional"))
      (node (ref "J3") (pin "1") (pinfunction "1_1") (pintype "bidirectional"))
      (node (ref "J3") (pin "2") (pinfunction "2_2") (pintype "bidirectional"))
      (node (ref "J3") (pin "3") (pinfunction "3_3") (pintype "bidirectional"))
      (node (ref "J3") (pin "4") (pinfunction "4_4") (pintype "bidirectional"))
      (node (ref "J4") (pin "1") (pinfunction "1_1") (pintype "bidirectional"))
      (node (ref "J4") (pin "2") (pinfunction "2_2") (pintype "bidirectional"))
      (node (ref "J4") (pin "3") (pinfunction "3_3") (pintype "bidirectional"))
      (node (ref "J4") (pin "4") (pinfunction "4_4") (pintype "bidirectional"))
      (node (ref "JP3") (pin "2") (pinfunction "2_2") (pintype "passive"))
      (node (ref "JP3") (pin "4") (pinfunction "4_4") (pintype "passive"))
      (node (ref "JTAG_ROCKET") (pin "10") (pinfunction "10_10") (pintype "passive"))
      (node (ref "JTAG_ROCKET") (pin "12") (pinfunction "12_12") (pintype "passive"))
      (node (ref "JTAG_ROCKET") (pin "14") (pinfunction "14_14") (pintype "passive"))
      (node (ref "JTAG_ROCKET") (pin "16") (pinfunction "16_16") (pintype "passive"))
      (node (ref "JTAG_ROCKET") (pin "18") (pinfunction "18_18") (pintype "passive"))
      (node (ref "JTAG_ROCKET") (pin "20") (pinfunction "20_20") (pintype "passive"))
      (node (ref "JTAG_ROCKET") (pin "4") (pinfunction "4_4") (pintype "passive"))
      (node (ref "JTAG_ROCKET") (pin "6") (pinfunction "6_6") (pintype "passive"))
      (node (ref "JTAG_ROCKET") (pin "8") (pinfunction "8_8") (pintype "passive"))
      (node (ref "JTAG_SERV") (pin "10") (pinfunction "10_10") (pintype "passive"))
      (node (ref "JTAG_SERV") (pin "12") (pinfunction "12_12") (pintype "passive"))
      (node (ref "JTAG_SERV") (pin "14") (pinfunction "14_14") (pintype "passive"))
      (node (ref "JTAG_SERV") (pin "16") (pinfunction "16_16") (pintype "passive"))
      (node (ref "JTAG_SERV") (pin "18") (pinfunction "18_18") (pintype "passive"))
      (node (ref "JTAG_SERV") (pin "20") (pinfunction "20_20") (pintype "passive"))
      (node (ref "JTAG_SERV") (pin "4") (pinfunction "4_4") (pintype "passive"))
      (node (ref "JTAG_SERV") (pin "6") (pinfunction "6_6") (pintype "passive"))
      (node (ref "JTAG_SERV") (pin "8") (pinfunction "8_8") (pintype "passive"))
      (node (ref "R14") (pin "1") (pinfunction "1_1") (pintype "passive"))
      (node (ref "R3") (pin "1") (pinfunction "1_1") (pintype "passive"))
      (node (ref "R4") (pin "1") (pinfunction "1_1") (pintype "passive"))
      (node (ref "R5") (pin "1") (pinfunction "1_1") (pintype "passive"))
      (node (ref "R6") (pin "1") (pinfunction "1_1") (pintype "passive"))
      (node (ref "ROCKET_FPGA") (pin "12") (pinfunction "12_12") (pintype "passive"))
      (node (ref "ROCKET_FPGA") (pin "30") (pinfunction "30_30") (pintype "passive"))
      (node (ref "S1") (pin "3") (pinfunction "ON_2_3") (pintype "bidirectional"))
      (node (ref "S2") (pin "3") (pinfunction "ON_2_3") (pintype "bidirectional"))
      (node (ref "S3") (pin "3") (pinfunction "ON_2_3") (pintype "bidirectional"))
      (node (ref "SD_CARD") (pin "3") (pinfunction "3_3") (pintype "passive"))
      (node (ref "SD_CARD") (pin "4") (pinfunction "4_4") (pintype "passive"))
      (node (ref "SOCKET_1") (pin "12") (pinfunction "12_12") (pintype "bidirectional"))
      (node (ref "SOCKET_1") (pin "2") (pinfunction "2_2") (pintype "bidirectional"))
      (node (ref "SOCKET_1") (pin "22") (pinfunction "22_22") (pintype "bidirectional"))
      (node (ref "SOCKET_1") (pin "31") (pinfunction "31_31") (pintype "bidirectional"))
      (node (ref "SOCKET_1") (pin "41") (pinfunction "41_41") (pintype "bidirectional"))
      (node (ref "SOCKET_1") (pin "51") (pinfunction "51_51") (pintype "bidirectional"))
      (node (ref "SOCKET_2") (pin "12") (pinfunction "12_12") (pintype "bidirectional"))
      (node (ref "SOCKET_2") (pin "2") (pinfunction "2_2") (pintype "bidirectional"))
      (node (ref "SOCKET_2") (pin "22") (pinfunction "22_22") (pintype "bidirectional"))
      (node (ref "SOCKET_2") (pin "31") (pinfunction "31_31") (pintype "bidirectional"))
      (node (ref "SOCKET_2") (pin "42") (pinfunction "42_42") (pintype "bidirectional"))
      (node (ref "SOCKET_2") (pin "51") (pinfunction "51_51") (pintype "bidirectional"))
      (node (ref "SOCKET_3") (pin "10") (pinfunction "10_10") (pintype "bidirectional"))
      (node (ref "SOCKET_3") (pin "12") (pinfunction "12_12") (pintype "bidirectional"))
      (node (ref "SOCKET_3") (pin "2") (pinfunction "2_2") (pintype "bidirectional"))
      (node (ref "SOCKET_3") (pin "22") (pinfunction "22_22") (pintype "bidirectional"))
      (node (ref "SOCKET_3") (pin "31") (pinfunction "31_31") (pintype "bidirectional"))
      (node (ref "SOCKET_3") (pin "41") (pinfunction "41_41") (pintype "bidirectional"))
      (node (ref "SOCKET_3") (pin "51") (pinfunction "51_51") (pintype "bidirectional"))
      (node (ref "SOCKET_4") (pin "12") (pinfunction "12_12") (pintype "bidirectional"))
      (node (ref "SOCKET_4") (pin "2") (pinfunction "2_2") (pintype "bidirectional"))
      (node (ref "SOCKET_4") (pin "22") (pinfunction "22_22") (pintype "bidirectional"))
      (node (ref "SOCKET_4") (pin "31") (pinfunction "31_31") (pintype "bidirectional"))
      (node (ref "SOCKET_4") (pin "41") (pinfunction "41_41") (pintype "bidirectional"))
      (node (ref "SOCKET_4") (pin "51") (pinfunction "51_51") (pintype "bidirectional"))
      (node (ref "USB-UART_1") (pin "1") (pinfunction "1_1") (pintype "passive"))
      (node (ref "USB-UART_SERV_1") (pin "1") (pinfunction "1_1") (pintype "passive"))
      (node (ref "Y1") (pin "2") (pinfunction "GND_1_2") (pintype "bidirectional"))
      (node (ref "Y1") (pin "4") (pinfunction "GND_2_4") (pintype "bidirectional"))
    )
    (net (code "30") (name "GPIO_GPIO_0") (class "Default")
      (node (ref "GPIO_2") (pin "1") (pinfunction "1_1") (pintype "passive"))
      (node (ref "SOCKET_3") (pin "50") (pinfunction "50_50") (pintype "bidirectional"))
    )
    (net (code "31") (name "GPIO_GPIO_1") (class "Default")
      (node (ref "GPIO_2") (pin "2") (pinfunction "2_2") (pintype "passive"))
      (node (ref "SOCKET_3") (pin "49") (pinfunction "49_49") (pintype "bidirectional"))
    )
    (net (code "32") (name "JTAG_TCK") (class "Default")
      (node (ref "J6") (pin "4") (pinfunction "4_4") (pintype "passive"))
      (node (ref "JTAG_ROCKET") (pin "9") (pinfunction "9_9") (pintype "passive"))
      (node (ref "SOCKET_3") (pin "43") (pinfunction "43_43") (pintype "bidirectional"))
    )
    (net (code "33") (name "JTAG_TCK_FPGA") (class "Default")
      (node (ref "J6") (pin "3") (pinfunction "3_3") (pintype "passive"))
      (node (ref "ROCKET_FPGA") (pin "31") (pinfunction "31_31") (pintype "passive"))
    )
    (net (code "34") (name "JTAG_TDI") (class "Default")
      (node (ref "J6") (pin "6") (pinfunction "6_6") (pintype "passive"))
      (node (ref "JTAG_ROCKET") (pin "5") (pinfunction "5_5") (pintype "passive"))
      (node (ref "SOCKET_3") (pin "44") (pinfunction "44_44") (pintype "bidirectional"))
    )
    (net (code "35") (name "JTAG_TDI_FPGA") (class "Default")
      (node (ref "J6") (pin "5") (pinfunction "5_5") (pintype "passive"))
      (node (ref "ROCKET_FPGA") (pin "32") (pinfunction "32_32") (pintype "passive"))
    )
    (net (code "36") (name "JTAG_TDO") (class "Default")
      (node (ref "J6") (pin "10") (pinfunction "10_10") (pintype "passive"))
      (node (ref "JTAG_ROCKET") (pin "13") (pinfunction "13_13") (pintype "passive"))
      (node (ref "SOCKET_3") (pin "46") (pinfunction "46_46") (pintype "bidirectional"))
    )
    (net (code "37") (name "JTAG_TDO_FPGA") (class "Default")
      (node (ref "J6") (pin "9") (pinfunction "9_9") (pintype "passive"))
      (node (ref "ROCKET_FPGA") (pin "34") (pinfunction "34_34") (pintype "passive"))
    )
    (net (code "38") (name "JTAG_TMS") (class "Default")
      (node (ref "J6") (pin "2") (pinfunction "2_2") (pintype "passive"))
      (node (ref "JTAG_ROCKET") (pin "7") (pinfunction "7_7") (pintype "passive"))
      (node (ref "SOCKET_3") (pin "40") (pinfunction "40_40") (pintype "bidirectional"))
    )
    (net (code "39") (name "JTAG_TMS_FPGA") (class "Default")
      (node (ref "J6") (pin "1") (pinfunction "1_1") (pintype "passive"))
      (node (ref "ROCKET_FPGA") (pin "28") (pinfunction "28_28") (pintype "passive"))
    )
    (net (code "40") (name "JTAG_TRSTN") (class "Default")
      (node (ref "J6") (pin "8") (pinfunction "8_8") (pintype "passive"))
      (node (ref "JTAG_ROCKET") (pin "3") (pinfunction "3_3") (pintype "passive"))
      (node (ref "SOCKET_3") (pin "45") (pinfunction "45_45") (pintype "bidirectional"))
    )
    (net (code "41") (name "JTAG_TRSTN_FPGA") (class "Default")
      (node (ref "J6") (pin "7") (pinfunction "7_7") (pintype "passive"))
      (node (ref "ROCKET_FPGA") (pin "33") (pinfunction "33_33") (pintype "passive"))
    )
    (net (code "42") (name "LEROS_PAD_CPU_RST_N_0") (class "Default")
      (node (ref "LEROS_RST") (pin "1") (pinfunction "1_1") (pintype "passive"))
      (node (ref "SOCKET_2") (pin "37") (pinfunction "37_37") (pintype "bidirectional"))
    )
    (net (code "43") (name "LEROS_PAD_I_CLK_0") (class "Default")
      (node (ref "LEROS_CLOCK") (pin "2") (pinfunction "2_2") (pintype "passive"))
      (node (ref "SOCKET_2") (pin "36") (pinfunction "36_36") (pintype "bidirectional"))
    )
    (net (code "44") (name "LEROS_PAD_I_SPI_LOADER_CLK_0") (class "Default")
      (node (ref "FPGA_LEROS") (pin "5") (pinfunction "5_5") (pintype "passive"))
      (node (ref "SOCKET_2") (pin "49") (pinfunction "49_49") (pintype "bidirectional"))
    )
    (net (code "45") (name "LEROS_PAD_I_SPI_LOADER_CS_0") (class "Default")
      (node (ref "FPGA_LEROS") (pin "6") (pinfunction "6_6") (pintype "passive"))
      (node (ref "SOCKET_2") (pin "50") (pinfunction "50_50") (pintype "bidirectional"))
    )
    (net (code "46") (name "LEROS_PAD_I_SPI_LOADER_MOSI_0") (class "Default")
      (node (ref "FPGA_LEROS") (pin "7") (pinfunction "7_7") (pintype "passive"))
      (node (ref "SOCKET_3") (pin "3") (pinfunction "3_3") (pintype "bidirectional"))
    )
    (net (code "47") (name "LEROS_PAD_I_SPI_MISO_0") (class "Default")
      (node (ref "FPGA_LEROS") (pin "11") (pinfunction "11_11") (pintype "passive"))
      (node (ref "SOCKET_3") (pin "7") (pinfunction "7_7") (pintype "bidirectional"))
    )
    (net (code "48") (name "LEROS_PAD_LOADER_RST_N_0") (class "Default")
      (node (ref "JP1") (pin "2") (pinfunction "2_2") (pintype "passive"))
      (node (ref "SOCKET_2") (pin "38") (pinfunction "38_38") (pintype "bidirectional"))
    )
    (net (code "49") (name "LEROS_PAD_LOADER_RST_N_0_FPGA") (class "Default")
      (node (ref "FPGA_LEROS") (pin "4") (pinfunction "4_4") (pintype "passive"))
      (node (ref "JP1") (pin "1") (pinfunction "1_1") (pintype "passive"))
    )
    (net (code "50") (name "LEROS_PAD_OLEDG_0_0") (class "Default")
      (node (ref "LED1") (pin "A") (pinfunction "A_A") (pintype "passive"))
      (node (ref "LEROS_LEDS") (pin "1") (pinfunction "1_1") (pintype "passive"))
      (node (ref "SOCKET_2") (pin "39") (pinfunction "39_39") (pintype "bidirectional"))
    )
    (net (code "51") (name "LEROS_PAD_OLEDG_0_1") (class "Default")
      (node (ref "LED2") (pin "A") (pinfunction "A_A") (pintype "passive"))
      (node (ref "LEROS_LEDS") (pin "2") (pinfunction "2_2") (pintype "passive"))
      (node (ref "SOCKET_2") (pin "40") (pinfunction "40_40") (pintype "bidirectional"))
    )
    (net (code "52") (name "LEROS_PAD_OLEDG_0_2") (class "Default")
      (node (ref "LED3") (pin "A") (pinfunction "A_A") (pintype "passive"))
      (node (ref "LEROS_LEDS") (pin "3") (pinfunction "3_3") (pintype "passive"))
      (node (ref "SOCKET_2") (pin "43") (pinfunction "43_43") (pintype "bidirectional"))
    )
    (net (code "53") (name "LEROS_PAD_OLEDG_0_3") (class "Default")
      (node (ref "LED4") (pin "A") (pinfunction "A_A") (pintype "passive"))
      (node (ref "LEROS_LEDS") (pin "4") (pinfunction "4_4") (pintype "passive"))
      (node (ref "SOCKET_2") (pin "44") (pinfunction "44_44") (pintype "bidirectional"))
    )
    (net (code "54") (name "LEROS_PAD_OLEDG_0_4") (class "Default")
      (node (ref "LEROS_LEDS") (pin "5") (pinfunction "5_5") (pintype "passive"))
      (node (ref "SOCKET_2") (pin "45") (pinfunction "45_45") (pintype "bidirectional"))
    )
    (net (code "55") (name "LEROS_PAD_OLEDG_0_5") (class "Default")
      (node (ref "LEROS_LEDS") (pin "6") (pinfunction "6_6") (pintype "passive"))
      (node (ref "SOCKET_2") (pin "46") (pinfunction "46_46") (pintype "bidirectional"))
    )
    (net (code "56") (name "LEROS_PAD_OLEDG_0_6") (class "Default")
      (node (ref "LEROS_LEDS") (pin "7") (pinfunction "7_7") (pintype "passive"))
      (node (ref "SOCKET_2") (pin "47") (pinfunction "47_47") (pintype "bidirectional"))
    )
    (net (code "57") (name "LEROS_PAD_OLEDG_0_7") (class "Default")
      (node (ref "LEROS_LEDS") (pin "8") (pinfunction "8_8") (pintype "passive"))
      (node (ref "SOCKET_2") (pin "48") (pinfunction "48_48") (pintype "bidirectional"))
    )
    (net (code "58") (name "LEROS_PAD_O_SPI_CLK_0") (class "Default")
      (node (ref "FPGA_LEROS") (pin "8") (pinfunction "8_8") (pintype "passive"))
      (node (ref "SOCKET_3") (pin "4") (pinfunction "4_4") (pintype "bidirectional"))
    )
    (net (code "59") (name "LEROS_PAD_O_SPI_CS_0") (class "Default")
      (node (ref "FPGA_LEROS") (pin "9") (pinfunction "9_9") (pintype "passive"))
      (node (ref "SOCKET_3") (pin "5") (pinfunction "5_5") (pintype "bidirectional"))
    )
    (net (code "60") (name "LEROS_PAD_O_SPI_MOSI_0") (class "Default")
      (node (ref "FPGA_LEROS") (pin "10") (pinfunction "10_10") (pintype "passive"))
      (node (ref "SOCKET_3") (pin "6") (pinfunction "6_6") (pintype "bidirectional"))
    )
    (net (code "61") (name "LEROS_PAD_SRAM_LOADED_0") (class "Default")
      (node (ref "J5") (pin "2") (pinfunction "2_2") (pintype "passive"))
      (node (ref "SOCKET_3") (pin "8") (pinfunction "8_8") (pintype "bidirectional"))
    )
    (net (code "62") (name "LEROS_PAD_SRAM_LOADED_0_FPGA") (class "Default")
      (node (ref "FPGA_LEROS") (pin "12") (pinfunction "12_12") (pintype "passive"))
      (node (ref "J5") (pin "1") (pinfunction "1_1") (pintype "passive"))
    )
    (net (code "63") (name "LEROS_PAD_VDD_0") (class "Default")
      (node (ref "C12") (pin "1") (pinfunction "1_1") (pintype "passive"))
      (node (ref "C13") (pin "1") (pinfunction "1_1") (pintype "passive"))
      (node (ref "POWER_LEROS") (pin "2") (pinfunction "2_2") (pintype "passive"))
      (node (ref "SOCKET_2") (pin "52") (pinfunction "52_52") (pintype "bidirectional"))
    )
    (net (code "64") (name "LEROS_PAD_VDD_DM_RAM_0") (class "Default")
      (node (ref "C23") (pin "1") (pinfunction "1_1") (pintype "passive"))
      (node (ref "C24") (pin "1") (pinfunction "1_1") (pintype "passive"))
      (node (ref "POWER_LEROS") (pin "6") (pinfunction "6_6") (pintype "passive"))
      (node (ref "SOCKET_3") (pin "11") (pinfunction "11_11") (pintype "bidirectional"))
    )
    (net (code "65") (name "LEROS_PAD_VDD_IM_RAM_0") (class "Default")
      (node (ref "C11") (pin "1") (pinfunction "1_1") (pintype "passive"))
      (node (ref "C14") (pin "1") (pinfunction "1_1") (pintype "passive"))
      (node (ref "POWER_LEROS") (pin "4") (pinfunction "4_4") (pintype "passive"))
      (node (ref "SOCKET_3") (pin "9") (pinfunction "9_9") (pintype "bidirectional"))
    )
    (net (code "66") (name "MEMSER_PAD_IN_READY") (class "Default")
      (node (ref "ROCKET_FPGA") (pin "24") (pinfunction "24_24") (pintype "passive"))
      (node (ref "SOCKET_3") (pin "36") (pinfunction "36_36") (pintype "bidirectional"))
    )
    (net (code "67") (name "MEMSER_PAD_IN_VALID") (class "Default")
      (node (ref "ROCKET_FPGA") (pin "22") (pinfunction "22_22") (pintype "passive"))
      (node (ref "SOCKET_3") (pin "34") (pinfunction "34_34") (pintype "bidirectional"))
    )
    (net (code "68") (name "MEMSER_PAD_OUT_BITS_0") (class "Default")
      (node (ref "ROCKET_FPGA") (pin "2") (pinfunction "2_2") (pintype "passive"))
      (node (ref "SOCKET_3") (pin "13") (pinfunction "13_13") (pintype "bidirectional"))
    )
    (net (code "69") (name "MEMSER_PAD_OUT_BITS_1") (class "Default")
      (node (ref "ROCKET_FPGA") (pin "4") (pinfunction "4_4") (pintype "passive"))
      (node (ref "SOCKET_3") (pin "14") (pinfunction "14_14") (pintype "bidirectional"))
    )
    (net (code "70") (name "MEMSER_PAD_OUT_BITS_2") (class "Default")
      (node (ref "ROCKET_FPGA") (pin "5") (pinfunction "5_5") (pintype "passive"))
      (node (ref "SOCKET_3") (pin "15") (pinfunction "15_15") (pintype "bidirectional"))
    )
    (net (code "71") (name "MEMSER_PAD_OUT_BITS_3") (class "Default")
      (node (ref "ROCKET_FPGA") (pin "6") (pinfunction "6_6") (pintype "passive"))
      (node (ref "SOCKET_3") (pin "16") (pinfunction "16_16") (pintype "bidirectional"))
    )
    (net (code "72") (name "MEMSER_PAD_OUT_BITS_4") (class "Default")
      (node (ref "ROCKET_FPGA") (pin "7") (pinfunction "7_7") (pintype "passive"))
      (node (ref "SOCKET_3") (pin "17") (pinfunction "17_17") (pintype "bidirectional"))
    )
    (net (code "73") (name "MEMSER_PAD_OUT_BITS_5") (class "Default")
      (node (ref "ROCKET_FPGA") (pin "8") (pinfunction "8_8") (pintype "passive"))
      (node (ref "SOCKET_3") (pin "18") (pinfunction "18_18") (pintype "bidirectional"))
    )
    (net (code "74") (name "MEMSER_PAD_OUT_BITS_6") (class "Default")
      (node (ref "ROCKET_FPGA") (pin "9") (pinfunction "9_9") (pintype "passive"))
      (node (ref "SOCKET_3") (pin "19") (pinfunction "19_19") (pintype "bidirectional"))
    )
    (net (code "75") (name "MEMSER_PAD_OUT_BITS_7") (class "Default")
      (node (ref "ROCKET_FPGA") (pin "10") (pinfunction "10_10") (pintype "passive"))
      (node (ref "SOCKET_3") (pin "20") (pinfunction "20_20") (pintype "bidirectional"))
    )
    (net (code "76") (name "MEMSER_PAD_OUT_READY") (class "Default")
      (node (ref "ROCKET_FPGA") (pin "21") (pinfunction "21_21") (pintype "passive"))
      (node (ref "SOCKET_3") (pin "33") (pinfunction "33_33") (pintype "bidirectional"))
    )
    (net (code "77") (name "MEMSER_PAD_OUT_VALID") (class "Default")
      (node (ref "ROCKET_FPGA") (pin "23") (pinfunction "23_23") (pintype "passive"))
      (node (ref "SOCKET_3") (pin "35") (pinfunction "35_35") (pintype "bidirectional"))
    )
    (net (code "78") (name "MEMSER_SYSTEM_MEMSER_OUTER_IO_IN_BITS_PAD_IN_BITS_0") (class "Default")
      (node (ref "ROCKET_FPGA") (pin "13") (pinfunction "13_13") (pintype "passive"))
      (node (ref "SOCKET_3") (pin "23") (pinfunction "23_23") (pintype "bidirectional"))
    )
    (net (code "79") (name "MEMSER_SYSTEM_MEMSER_OUTER_IO_IN_BITS_PAD_IN_BITS_1") (class "Default")
      (node (ref "ROCKET_FPGA") (pin "14") (pinfunction "14_14") (pintype "passive"))
      (node (ref "SOCKET_3") (pin "24") (pinfunction "24_24") (pintype "bidirectional"))
    )
    (net (code "80") (name "MEMSER_SYSTEM_MEMSER_OUTER_IO_IN_BITS_PAD_IN_BITS_2") (class "Default")
      (node (ref "ROCKET_FPGA") (pin "15") (pinfunction "15_15") (pintype "passive"))
      (node (ref "SOCKET_3") (pin "25") (pinfunction "25_25") (pintype "bidirectional"))
    )
    (net (code "81") (name "MEMSER_SYSTEM_MEMSER_OUTER_IO_IN_BITS_PAD_IN_BITS_3") (class "Default")
      (node (ref "ROCKET_FPGA") (pin "16") (pinfunction "16_16") (pintype "passive"))
      (node (ref "SOCKET_3") (pin "26") (pinfunction "26_26") (pintype "bidirectional"))
    )
    (net (code "82") (name "MEMSER_SYSTEM_MEMSER_OUTER_IO_IN_BITS_PAD_IN_BITS_4") (class "Default")
      (node (ref "ROCKET_FPGA") (pin "17") (pinfunction "17_17") (pintype "passive"))
      (node (ref "SOCKET_3") (pin "27") (pinfunction "27_27") (pintype "bidirectional"))
    )
    (net (code "83") (name "MEMSER_SYSTEM_MEMSER_OUTER_IO_IN_BITS_PAD_IN_BITS_5") (class "Default")
      (node (ref "ROCKET_FPGA") (pin "18") (pinfunction "18_18") (pintype "passive"))
      (node (ref "SOCKET_3") (pin "28") (pinfunction "28_28") (pintype "bidirectional"))
    )
    (net (code "84") (name "MEMSER_SYSTEM_MEMSER_OUTER_IO_IN_BITS_PAD_IN_BITS_6") (class "Default")
      (node (ref "ROCKET_FPGA") (pin "19") (pinfunction "19_19") (pintype "passive"))
      (node (ref "SOCKET_3") (pin "29") (pinfunction "29_29") (pintype "bidirectional"))
    )
    (net (code "85") (name "MEMSER_SYSTEM_MEMSER_OUTER_IO_IN_BITS_PAD_IN_BITS_7") (class "Default")
      (node (ref "ROCKET_FPGA") (pin "20") (pinfunction "20_20") (pintype "passive"))
      (node (ref "SOCKET_3") (pin "30") (pinfunction "30_30") (pintype "bidirectional"))
    )
    (net (code "86") (name "Net-(IC7-A1)") (class "Default")
      (node (ref "IC7") (pin "1") (pinfunction "A1_1") (pintype "bidirectional"))
      (node (ref "SERV_SPI") (pin "2") (pinfunction "2_2") (pintype "passive"))
    )
    (net (code "87") (name "Net-(IC7-A2)") (class "Default")
      (node (ref "IC7") (pin "3") (pinfunction "A2_3") (pintype "bidirectional"))
      (node (ref "SERV_SPI") (pin "4") (pinfunction "4_4") (pintype "passive"))
    )
    (net (code "88") (name "Net-(IC7-A3)") (class "Default")
      (node (ref "IC7") (pin "4") (pinfunction "A3_4") (pintype "bidirectional"))
      (node (ref "SERV_SPI") (pin "6") (pinfunction "6_6") (pintype "passive"))
    )
    (net (code "89") (name "Net-(IC7-A4)") (class "Default")
      (node (ref "IC7") (pin "5") (pinfunction "A4_5") (pintype "bidirectional"))
      (node (ref "SERV_SPI") (pin "8") (pinfunction "8_8") (pintype "passive"))
    )
    (net (code "90") (name "Net-(IC7-A5)") (class "Default")
      (node (ref "IC7") (pin "6") (pinfunction "A5_6") (pintype "bidirectional"))
      (node (ref "SERV_FLASH") (pin "2") (pinfunction "2_2") (pintype "passive"))
    )
    (net (code "91") (name "Net-(IC7-A6)") (class "Default")
      (node (ref "IC7") (pin "7") (pinfunction "A6_7") (pintype "bidirectional"))
      (node (ref "SERV_FLASH") (pin "4") (pinfunction "4_4") (pintype "passive"))
    )
    (net (code "92") (name "Net-(IC7-A7)") (class "Default")
      (node (ref "IC7") (pin "8") (pinfunction "A7_8") (pintype "bidirectional"))
      (node (ref "SERV_FLASH") (pin "6") (pinfunction "6_6") (pintype "passive"))
    )
    (net (code "93") (name "Net-(IC7-A8)") (class "Default")
      (node (ref "IC7") (pin "9") (pinfunction "A8_9") (pintype "bidirectional"))
      (node (ref "SERV_FLASH") (pin "8") (pinfunction "8_8") (pintype "passive"))
    )
    (net (code "94") (name "Net-(IC10-A2)") (class "Default")
      (node (ref "IC10") (pin "3") (pinfunction "A2_3") (pintype "bidirectional"))
      (node (ref "SERV_UART") (pin "2") (pinfunction "2_2") (pintype "passive"))
    )
    (net (code "95") (name "Net-(IC10-A3)") (class "Default")
      (node (ref "IC10") (pin "4") (pinfunction "A3_4") (pintype "bidirectional"))
      (node (ref "SERV_UART") (pin "4") (pinfunction "4_4") (pintype "passive"))
    )
    (net (code "96") (name "Net-(IC10-A4)") (class "Default")
      (node (ref "IC10") (pin "5") (pinfunction "A4_5") (pintype "bidirectional"))
      (node (ref "SERV_JTAG") (pin "2") (pinfunction "2_2") (pintype "passive"))
    )
    (net (code "97") (name "Net-(IC10-A5)") (class "Default")
      (node (ref "IC10") (pin "6") (pinfunction "A5_6") (pintype "bidirectional"))
      (node (ref "SERV_JTAG") (pin "4") (pinfunction "4_4") (pintype "passive"))
    )
    (net (code "98") (name "Net-(IC10-A6)") (class "Default")
      (node (ref "IC10") (pin "7") (pinfunction "A6_7") (pintype "bidirectional"))
      (node (ref "SERV_JTAG") (pin "6") (pinfunction "6_6") (pintype "passive"))
    )
    (net (code "99") (name "Net-(IC10-A7)") (class "Default")
      (node (ref "IC10") (pin "8") (pinfunction "A7_8") (pintype "bidirectional"))
      (node (ref "SERV_JTAG") (pin "8") (pinfunction "8_8") (pintype "passive"))
    )
    (net (code "100") (name "Net-(IC10-A8)") (class "Default")
      (node (ref "IC10") (pin "9") (pinfunction "A8_9") (pintype "bidirectional"))
      (node (ref "SERV_JTAG") (pin "10") (pinfunction "10_10") (pintype "passive"))
    )
    (net (code "101") (name "Net-(J5-Pad3)") (class "Default")
      (node (ref "J5") (pin "3") (pinfunction "3_3") (pintype "passive"))
      (node (ref "LOADED") (pin "A") (pinfunction "A_A") (pintype "passive"))
    )
    (net (code "102") (name "Net-(LED1-PadC)") (class "Default")
      (node (ref "LED1") (pin "C") (pinfunction "C_C") (pintype "passive"))
      (node (ref "R14") (pin "2") (pinfunction "2_2") (pintype "passive"))
    )
    (net (code "103") (name "Net-(LED2-PadC)") (class "Default")
      (node (ref "LED2") (pin "C") (pinfunction "C_C") (pintype "passive"))
      (node (ref "R3") (pin "2") (pinfunction "2_2") (pintype "passive"))
    )
    (net (code "104") (name "Net-(LED3-PadC)") (class "Default")
      (node (ref "LED3") (pin "C") (pinfunction "C_C") (pintype "passive"))
      (node (ref "R4") (pin "2") (pinfunction "2_2") (pintype "passive"))
    )
    (net (code "105") (name "Net-(LED4-PadC)") (class "Default")
      (node (ref "LED4") (pin "C") (pinfunction "C_C") (pintype "passive"))
      (node (ref "R5") (pin "2") (pinfunction "2_2") (pintype "passive"))
    )
    (net (code "106") (name "Net-(LOADED-PadC)") (class "Default")
      (node (ref "LOADED") (pin "C") (pinfunction "C_C") (pintype "passive"))
      (node (ref "R6") (pin "2") (pinfunction "2_2") (pintype "passive"))
    )
    (net (code "107") (name "Net-(S1-COM)") (class "Default")
      (node (ref "R1") (pin "1") (pinfunction "1_1") (pintype "passive"))
      (node (ref "S1") (pin "2") (pinfunction "COM_2") (pintype "bidirectional"))
      (node (ref "SERV_RST") (pin "2") (pinfunction "2_2") (pintype "passive"))
    )
    (net (code "108") (name "Net-(S2-COM)") (class "Default")
      (node (ref "LEROS_RST") (pin "2") (pinfunction "2_2") (pintype "passive"))
      (node (ref "R2") (pin "1") (pinfunction "1_1") (pintype "passive"))
      (node (ref "S2") (pin "2") (pinfunction "COM_2") (pintype "bidirectional"))
    )
    (net (code "109") (name "Net-(S3-COM)") (class "Default")
      (node (ref "JP1") (pin "3") (pinfunction "3_3") (pintype "passive"))
      (node (ref "R11") (pin "1") (pinfunction "1_1") (pintype "passive"))
      (node (ref "S3") (pin "2") (pinfunction "COM_2") (pintype "bidirectional"))
    )
    (net (code "110") (name "PUF_PUF_TG_0_0") (class "Default")
      (node (ref "PUF") (pin "1") (pinfunction "1_1") (pintype "passive"))
      (node (ref "SOCKET_1") (pin "33") (pinfunction "33_33") (pintype "bidirectional"))
    )
    (net (code "111") (name "PUF_PUF_TG_0_1") (class "Default")
      (node (ref "PUF") (pin "2") (pinfunction "2_2") (pintype "passive"))
      (node (ref "SOCKET_1") (pin "34") (pinfunction "34_34") (pintype "bidirectional"))
    )
    (net (code "112") (name "PUF_PUF_TG_0_2") (class "Default")
      (node (ref "PUF") (pin "3") (pinfunction "3_3") (pintype "passive"))
      (node (ref "SOCKET_1") (pin "35") (pinfunction "35_35") (pintype "bidirectional"))
    )
    (net (code "113") (name "PUF_PUF_TG_0_3") (class "Default")
      (node (ref "PUF") (pin "4") (pinfunction "4_4") (pintype "passive"))
      (node (ref "SOCKET_1") (pin "36") (pinfunction "36_36") (pintype "bidirectional"))
    )
    (net (code "114") (name "PUF_PUF_TG_0_4") (class "Default")
      (node (ref "PUF") (pin "5") (pinfunction "5_5") (pintype "passive"))
      (node (ref "SOCKET_1") (pin "37") (pinfunction "37_37") (pintype "bidirectional"))
    )
    (net (code "115") (name "PUF_PUF_TG_0_5") (class "Default")
      (node (ref "PUF") (pin "6") (pinfunction "6_6") (pintype "passive"))
      (node (ref "SOCKET_1") (pin "38") (pinfunction "38_38") (pintype "bidirectional"))
    )
    (net (code "116") (name "PUF_PUF_TG_0_6") (class "Default")
      (node (ref "PUF") (pin "7") (pinfunction "7_7") (pintype "passive"))
      (node (ref "SOCKET_1") (pin "39") (pinfunction "39_39") (pintype "bidirectional"))
    )
    (net (code "117") (name "PUF_PUF_TG_0_7") (class "Default")
      (node (ref "PUF") (pin "8") (pinfunction "8_8") (pintype "passive"))
      (node (ref "SOCKET_1") (pin "40") (pinfunction "40_40") (pintype "bidirectional"))
    )
    (net (code "118") (name "PUF_PUF_VDDH_0") (class "Default")
      (node (ref "POWER_3.3V") (pin "2") (pinfunction "2_2") (pintype "passive"))
      (node (ref "SOCKET_1") (pin "30") (pinfunction "30_30") (pintype "bidirectional"))
    )
    (net (code "119") (name "SDRAMIO_SDRAM_ADDR_O_0") (class "Default")
      (node (ref "IC3") (pin "23") (pinfunction "A0_23") (pintype "bidirectional"))
      (node (ref "SOCKET_1") (pin "13") (pinfunction "13_13") (pintype "bidirectional"))
    )
    (net (code "120") (name "SDRAMIO_SDRAM_ADDR_O_1") (class "Default")
      (node (ref "IC3") (pin "24") (pinfunction "A1_24") (pintype "bidirectional"))
      (node (ref "SOCKET_1") (pin "14") (pinfunction "14_14") (pintype "bidirectional"))
    )
    (net (code "121") (name "SDRAMIO_SDRAM_ADDR_O_2") (class "Default")
      (node (ref "IC3") (pin "25") (pinfunction "A2_25") (pintype "bidirectional"))
      (node (ref "SOCKET_1") (pin "15") (pinfunction "15_15") (pintype "bidirectional"))
    )
    (net (code "122") (name "SDRAMIO_SDRAM_ADDR_O_3") (class "Default")
      (node (ref "IC3") (pin "26") (pinfunction "A3_26") (pintype "bidirectional"))
      (node (ref "SOCKET_1") (pin "16") (pinfunction "16_16") (pintype "bidirectional"))
    )
    (net (code "123") (name "SDRAMIO_SDRAM_ADDR_O_4") (class "Default")
      (node (ref "IC3") (pin "29") (pinfunction "A4_29") (pintype "bidirectional"))
      (node (ref "SOCKET_1") (pin "17") (pinfunction "17_17") (pintype "bidirectional"))
    )
    (net (code "124") (name "SDRAMIO_SDRAM_ADDR_O_5") (class "Default")
      (node (ref "IC3") (pin "30") (pinfunction "A5_30") (pintype "bidirectional"))
      (node (ref "SOCKET_1") (pin "18") (pinfunction "18_18") (pintype "bidirectional"))
    )
    (net (code "125") (name "SDRAMIO_SDRAM_ADDR_O_6") (class "Default")
      (node (ref "IC3") (pin "31") (pinfunction "A6_31") (pintype "bidirectional"))
      (node (ref "SOCKET_1") (pin "19") (pinfunction "19_19") (pintype "bidirectional"))
    )
    (net (code "126") (name "SDRAMIO_SDRAM_ADDR_O_7") (class "Default")
      (node (ref "IC3") (pin "32") (pinfunction "A7_32") (pintype "bidirectional"))
      (node (ref "SOCKET_1") (pin "20") (pinfunction "20_20") (pintype "bidirectional"))
    )
    (net (code "127") (name "SDRAMIO_SDRAM_ADDR_O_8") (class "Default")
      (node (ref "IC3") (pin "33") (pinfunction "A8_33") (pintype "bidirectional"))
      (node (ref "SOCKET_1") (pin "23") (pinfunction "23_23") (pintype "bidirectional"))
    )
    (net (code "128") (name "SDRAMIO_SDRAM_ADDR_O_9") (class "Default")
      (node (ref "IC3") (pin "34") (pinfunction "A9_34") (pintype "bidirectional"))
      (node (ref "SOCKET_1") (pin "24") (pinfunction "24_24") (pintype "bidirectional"))
    )
    (net (code "129") (name "SDRAMIO_SDRAM_ADDR_O_10") (class "Default")
      (node (ref "IC3") (pin "22") (pinfunction "A10/AP_22") (pintype "bidirectional"))
      (node (ref "SOCKET_1") (pin "25") (pinfunction "25_25") (pintype "bidirectional"))
    )
    (net (code "130") (name "SDRAMIO_SDRAM_ADDR_O_11") (class "Default")
      (node (ref "IC3") (pin "35") (pinfunction "A11_35") (pintype "bidirectional"))
      (node (ref "SOCKET_1") (pin "26") (pinfunction "26_26") (pintype "bidirectional"))
    )
    (net (code "131") (name "SDRAMIO_SDRAM_ADDR_O_12") (class "Default")
      (node (ref "IC3") (pin "36") (pinfunction "A12_36") (pintype "bidirectional"))
      (node (ref "SOCKET_1") (pin "27") (pinfunction "27_27") (pintype "bidirectional"))
    )
    (net (code "132") (name "SDRAMIO_SDRAM_BA_O_0") (class "Default")
      (node (ref "IC3") (pin "21") (pinfunction "BS1_21") (pintype "bidirectional"))
      (node (ref "SOCKET_1") (pin "28") (pinfunction "28_28") (pintype "bidirectional"))
    )
    (net (code "133") (name "SDRAMIO_SDRAM_BA_O_1") (class "Default")
      (node (ref "IC3") (pin "20") (pinfunction "BS0_20") (pintype "bidirectional"))
      (node (ref "SOCKET_1") (pin "29") (pinfunction "29_29") (pintype "bidirectional"))
    )
    (net (code "134") (name "SDRAMIO_SDRAM_CAS_O") (class "Default")
      (node (ref "IC3") (pin "17") (pinfunction "~{CAS}_17") (pintype "bidirectional"))
      (node (ref "SOCKET_1") (pin "7") (pinfunction "7_7") (pintype "bidirectional"))
    )
    (net (code "135") (name "SDRAMIO_SDRAM_CKE_O") (class "Default")
      (node (ref "IC3") (pin "37") (pinfunction "CKE_37") (pintype "bidirectional"))
      (node (ref "SOCKET_1") (pin "4") (pinfunction "4_4") (pintype "bidirectional"))
    )
    (net (code "136") (name "SDRAMIO_SDRAM_CLK_O") (class "Default")
      (node (ref "IC3") (pin "38") (pinfunction "CLK_38") (pintype "bidirectional"))
      (node (ref "SOCKET_1") (pin "3") (pinfunction "3_3") (pintype "bidirectional"))
    )
    (net (code "137") (name "SDRAMIO_SDRAM_CS_O") (class "Default")
      (node (ref "IC3") (pin "19") (pinfunction "~{CS}_19") (pintype "bidirectional"))
      (node (ref "SOCKET_1") (pin "5") (pinfunction "5_5") (pintype "bidirectional"))
    )
    (net (code "138") (name "SDRAMIO_SDRAM_DQM_O_0") (class "Default")
      (node (ref "IC3") (pin "15") (pinfunction "LDQM_15") (pintype "bidirectional"))
      (node (ref "SOCKET_1") (pin "9") (pinfunction "9_9") (pintype "bidirectional"))
    )
    (net (code "139") (name "SDRAMIO_SDRAM_DQM_O_1") (class "Default")
      (node (ref "IC3") (pin "39") (pinfunction "UDQM_39") (pintype "bidirectional"))
      (node (ref "SOCKET_1") (pin "10") (pinfunction "10_10") (pintype "bidirectional"))
    )
    (net (code "140") (name "SDRAMIO_SDRAM_RAS_O") (class "Default")
      (node (ref "IC3") (pin "18") (pinfunction "~{RAS}_18") (pintype "bidirectional"))
      (node (ref "SOCKET_1") (pin "6") (pinfunction "6_6") (pintype "bidirectional"))
    )
    (net (code "141") (name "SDRAMIO_SDRAM_WE_O") (class "Default")
      (node (ref "IC3") (pin "16") (pinfunction "~{WE}_16") (pintype "bidirectional"))
      (node (ref "SOCKET_1") (pin "8") (pinfunction "8_8") (pintype "bidirectional"))
    )
    (net (code "142") (name "SDRAMIO_SYSTEM_SDRAM_0_SDRAM_DATA_I_SDRAM_DATA_0") (class "Default")
      (node (ref "IC3") (pin "2") (pinfunction "DQ0_2") (pintype "bidirectional"))
      (node (ref "SOCKET_4") (pin "20") (pinfunction "20_20") (pintype "bidirectional"))
    )
    (net (code "143") (name "SDRAMIO_SYSTEM_SDRAM_0_SDRAM_DATA_I_SDRAM_DATA_1") (class "Default")
      (node (ref "IC3") (pin "4") (pinfunction "DQ1_4") (pintype "bidirectional"))
      (node (ref "SOCKET_4") (pin "19") (pinfunction "19_19") (pintype "bidirectional"))
    )
    (net (code "144") (name "SDRAMIO_SYSTEM_SDRAM_0_SDRAM_DATA_I_SDRAM_DATA_2") (class "Default")
      (node (ref "IC3") (pin "5") (pinfunction "DQ2_5") (pintype "bidirectional"))
      (node (ref "SOCKET_4") (pin "18") (pinfunction "18_18") (pintype "bidirectional"))
    )
    (net (code "145") (name "SDRAMIO_SYSTEM_SDRAM_0_SDRAM_DATA_I_SDRAM_DATA_3") (class "Default")
      (node (ref "IC3") (pin "7") (pinfunction "DQ3_7") (pintype "bidirectional"))
      (node (ref "SOCKET_4") (pin "17") (pinfunction "17_17") (pintype "bidirectional"))
    )
    (net (code "146") (name "SDRAMIO_SYSTEM_SDRAM_0_SDRAM_DATA_I_SDRAM_DATA_4") (class "Default")
      (node (ref "IC3") (pin "8") (pinfunction "DQ4_8") (pintype "bidirectional"))
      (node (ref "SOCKET_4") (pin "16") (pinfunction "16_16") (pintype "bidirectional"))
    )
    (net (code "147") (name "SDRAMIO_SYSTEM_SDRAM_0_SDRAM_DATA_I_SDRAM_DATA_5") (class "Default")
      (node (ref "IC3") (pin "10") (pinfunction "DQ5_10") (pintype "bidirectional"))
      (node (ref "SOCKET_4") (pin "15") (pinfunction "15_15") (pintype "bidirectional"))
    )
    (net (code "148") (name "SDRAMIO_SYSTEM_SDRAM_0_SDRAM_DATA_I_SDRAM_DATA_6") (class "Default")
      (node (ref "IC3") (pin "11") (pinfunction "DQ6_11") (pintype "bidirectional"))
      (node (ref "SOCKET_4") (pin "14") (pinfunction "14_14") (pintype "bidirectional"))
    )
    (net (code "149") (name "SDRAMIO_SYSTEM_SDRAM_0_SDRAM_DATA_I_SDRAM_DATA_7") (class "Default")
      (node (ref "IC3") (pin "13") (pinfunction "DQ7_13") (pintype "bidirectional"))
      (node (ref "SOCKET_4") (pin "13") (pinfunction "13_13") (pintype "bidirectional"))
    )
    (net (code "150") (name "SDRAMIO_SYSTEM_SDRAM_0_SDRAM_DATA_I_SDRAM_DATA_8") (class "Default")
      (node (ref "IC3") (pin "42") (pinfunction "DQ8_42") (pintype "bidirectional"))
      (node (ref "SOCKET_4") (pin "10") (pinfunction "10_10") (pintype "bidirectional"))
    )
    (net (code "151") (name "SDRAMIO_SYSTEM_SDRAM_0_SDRAM_DATA_I_SDRAM_DATA_9") (class "Default")
      (node (ref "IC3") (pin "44") (pinfunction "DQ9_44") (pintype "bidirectional"))
      (node (ref "SOCKET_4") (pin "9") (pinfunction "9_9") (pintype "bidirectional"))
    )
    (net (code "152") (name "SDRAMIO_SYSTEM_SDRAM_0_SDRAM_DATA_I_SDRAM_DATA_10") (class "Default")
      (node (ref "IC3") (pin "45") (pinfunction "DQ10_45") (pintype "bidirectional"))
      (node (ref "SOCKET_4") (pin "8") (pinfunction "8_8") (pintype "bidirectional"))
    )
    (net (code "153") (name "SDRAMIO_SYSTEM_SDRAM_0_SDRAM_DATA_I_SDRAM_DATA_11") (class "Default")
      (node (ref "IC3") (pin "47") (pinfunction "DQ11_47") (pintype "bidirectional"))
      (node (ref "SOCKET_4") (pin "7") (pinfunction "7_7") (pintype "bidirectional"))
    )
    (net (code "154") (name "SDRAMIO_SYSTEM_SDRAM_0_SDRAM_DATA_I_SDRAM_DATA_12") (class "Default")
      (node (ref "IC3") (pin "48") (pinfunction "DQ12_48") (pintype "bidirectional"))
      (node (ref "SOCKET_4") (pin "6") (pinfunction "6_6") (pintype "bidirectional"))
    )
    (net (code "155") (name "SDRAMIO_SYSTEM_SDRAM_0_SDRAM_DATA_I_SDRAM_DATA_13") (class "Default")
      (node (ref "IC3") (pin "50") (pinfunction "DQ13_50") (pintype "bidirectional"))
      (node (ref "SOCKET_4") (pin "5") (pinfunction "5_5") (pintype "bidirectional"))
    )
    (net (code "156") (name "SDRAMIO_SYSTEM_SDRAM_0_SDRAM_DATA_I_SDRAM_DATA_14") (class "Default")
      (node (ref "IC3") (pin "51") (pinfunction "DQ14_51") (pintype "bidirectional"))
      (node (ref "SOCKET_4") (pin "4") (pinfunction "4_4") (pintype "bidirectional"))
    )
    (net (code "157") (name "SDRAMIO_SYSTEM_SDRAM_0_SDRAM_DATA_I_SDRAM_DATA_15") (class "Default")
      (node (ref "IC3") (pin "53") (pinfunction "DQ15_53") (pintype "bidirectional"))
      (node (ref "SOCKET_4") (pin "3") (pinfunction "3_3") (pintype "bidirectional"))
    )
    (net (code "158") (name "SERV_FLASH_CIPO") (class "Default")
      (node (ref "FLASH_SERV") (pin "8") (pinfunction "8_8") (pintype "passive"))
      (node (ref "IC7") (pin "18") (pinfunction "B2_18") (pintype "bidirectional"))
    )
    (net (code "159") (name "SERV_FLASH_COPI") (class "Default")
      (node (ref "FLASH_SERV") (pin "10") (pinfunction "10_10") (pintype "passive"))
      (node (ref "IC7") (pin "17") (pinfunction "B3_17") (pintype "bidirectional"))
    )
    (net (code "160") (name "SERV_FLASH_CS") (class "Default")
      (node (ref "FLASH_SERV") (pin "12") (pinfunction "12_12") (pintype "passive"))
      (node (ref "IC7") (pin "20") (pinfunction "B1_20") (pintype "bidirectional"))
    )
    (net (code "161") (name "SERV_FLASH_SCK") (class "Default")
      (node (ref "FLASH_SERV") (pin "6") (pinfunction "6_6") (pintype "passive"))
      (node (ref "IC7") (pin "16") (pinfunction "B4_16") (pintype "bidirectional"))
    )
    (net (code "162") (name "SERV_JTAG_TCK") (class "Default")
      (node (ref "IC10") (pin "12") (pinfunction "B8_12") (pintype "bidirectional"))
      (node (ref "JTAG_SERV") (pin "9") (pinfunction "9_9") (pintype "passive"))
    )
    (net (code "163") (name "SERV_JTAG_TDI") (class "Default")
      (node (ref "IC10") (pin "13") (pinfunction "B7_13") (pintype "bidirectional"))
      (node (ref "JTAG_SERV") (pin "5") (pinfunction "5_5") (pintype "passive"))
    )
    (net (code "164") (name "SERV_JTAG_TDO") (class "Default")
      (node (ref "IC10") (pin "14") (pinfunction "B6_14") (pintype "bidirectional"))
      (node (ref "JTAG_SERV") (pin "13") (pinfunction "13_13") (pintype "passive"))
    )
    (net (code "165") (name "SERV_JTAG_TMS") (class "Default")
      (node (ref "IC10") (pin "15") (pinfunction "B5_15") (pintype "bidirectional"))
      (node (ref "JTAG_SERV") (pin "7") (pinfunction "7_7") (pintype "passive"))
    )
    (net (code "166") (name "SERV_JTAG_TRST") (class "Default")
      (node (ref "IC10") (pin "16") (pinfunction "B4_16") (pintype "bidirectional"))
      (node (ref "JTAG_SERV") (pin "3") (pinfunction "3_3") (pintype "passive"))
    )
    (net (code "167") (name "SERV_MOD_IO_ALL_DIPSW_PAD_ALL_DIPSW_0_0") (class "Default")
      (node (ref "EPAPER") (pin "1") (pinfunction "1_1") (pintype "passive"))
      (node (ref "SOCKET_2") (pin "15") (pinfunction "15_15") (pintype "bidirectional"))
    )
    (net (code "168") (name "SERV_MOD_IO_ALL_DIPSW_PAD_ALL_DIPSW_0_1") (class "Default")
      (node (ref "JP3") (pin "1") (pinfunction "1_1") (pintype "passive"))
      (node (ref "SOCKET_2") (pin "16") (pinfunction "16_16") (pintype "bidirectional"))
    )
    (net (code "169") (name "SERV_PAD_ALL_LEDS_0_0") (class "Default")
      (node (ref "EPAPER") (pin "3") (pinfunction "3_3") (pintype "passive"))
      (node (ref "SOCKET_2") (pin "13") (pinfunction "13_13") (pintype "bidirectional"))
    )
    (net (code "170") (name "SERV_PAD_ALL_LEDS_0_1") (class "Default")
      (node (ref "EPAPER") (pin "2") (pinfunction "2_2") (pintype "passive"))
      (node (ref "SOCKET_2") (pin "14") (pinfunction "14_14") (pintype "bidirectional"))
    )
    (net (code "171") (name "SERV_PAD_ALL_RESET_0") (class "Default")
      (node (ref "SERV_RST") (pin "1") (pinfunction "1_1") (pintype "passive"))
      (node (ref "SOCKET_2") (pin "9") (pinfunction "9_9") (pintype "bidirectional"))
    )
    (net (code "172") (name "SERV_PAD_CLOCK_0") (class "Default")
      (node (ref "SERV_CLK") (pin "2") (pinfunction "2_2") (pintype "passive"))
      (node (ref "SOCKET_2") (pin "10") (pinfunction "10_10") (pintype "bidirectional"))
    )
    (net (code "173") (name "SERV_PAD_I_SPIFLASH_CIPO_0") (class "Default")
      (node (ref "SERV_SPI") (pin "3") (pinfunction "3_3") (pintype "passive"))
      (node (ref "SOCKET_2") (pin "30") (pinfunction "30_30") (pintype "bidirectional"))
    )
    (net (code "174") (name "SERV_PAD_I_SPI_CIPO_0") (class "Default")
      (node (ref "JP3") (pin "3") (pinfunction "3_3") (pintype "passive"))
      (node (ref "SERV_FLASH") (pin "3") (pinfunction "3_3") (pintype "passive"))
      (node (ref "SOCKET_2") (pin "26") (pinfunction "26_26") (pintype "bidirectional"))
    )
    (net (code "175") (name "SERV_PAD_I_TCK_0") (class "Default")
      (node (ref "SERV_JTAG") (pin "9") (pinfunction "9_9") (pintype "passive"))
      (node (ref "SOCKET_2") (pin "17") (pinfunction "17_17") (pintype "bidirectional"))
    )
    (net (code "176") (name "SERV_PAD_I_TDI_0") (class "Default")
      (node (ref "SERV_JTAG") (pin "7") (pinfunction "7_7") (pintype "passive"))
      (node (ref "SOCKET_2") (pin "18") (pinfunction "18_18") (pintype "bidirectional"))
    )
    (net (code "177") (name "SERV_PAD_I_TMS_0") (class "Default")
      (node (ref "SERV_JTAG") (pin "3") (pinfunction "3_3") (pintype "passive"))
      (node (ref "SOCKET_2") (pin "20") (pinfunction "20_20") (pintype "bidirectional"))
    )
    (net (code "178") (name "SERV_PAD_I_TRST_0") (class "Default")
      (node (ref "SERV_JTAG") (pin "1") (pinfunction "1_1") (pintype "passive"))
      (node (ref "SOCKET_2") (pin "23") (pinfunction "23_23") (pintype "bidirectional"))
    )
    (net (code "179") (name "SERV_PAD_O_SPIFLASH_COPI_0") (class "Default")
      (node (ref "SERV_SPI") (pin "5") (pinfunction "5_5") (pintype "passive"))
      (node (ref "SOCKET_2") (pin "29") (pinfunction "29_29") (pintype "bidirectional"))
    )
    (net (code "180") (name "SERV_PAD_O_SPIFLASH_CS_0") (class "Default")
      (node (ref "SERV_SPI") (pin "1") (pinfunction "1_1") (pintype "passive"))
      (node (ref "SOCKET_2") (pin "33") (pinfunction "33_33") (pintype "bidirectional"))
    )
    (net (code "181") (name "SERV_PAD_O_SPIFLASH_SCK_0") (class "Default")
      (node (ref "SERV_SPI") (pin "7") (pinfunction "7_7") (pintype "passive"))
      (node (ref "SOCKET_2") (pin "28") (pinfunction "28_28") (pintype "bidirectional"))
    )
    (net (code "182") (name "SERV_PAD_O_SPI_COPI_0") (class "Default")
      (node (ref "SERV_FLASH") (pin "5") (pinfunction "5_5") (pintype "passive"))
      (node (ref "SOCKET_2") (pin "25") (pinfunction "25_25") (pintype "bidirectional"))
    )
    (net (code "183") (name "SERV_PAD_O_SPI_CS_0") (class "Default")
      (node (ref "SERV_FLASH") (pin "1") (pinfunction "1_1") (pintype "passive"))
      (node (ref "SOCKET_2") (pin "27") (pinfunction "27_27") (pintype "bidirectional"))
    )
    (net (code "184") (name "SERV_PAD_O_SPI_SCK_0") (class "Default")
      (node (ref "SERV_FLASH") (pin "7") (pinfunction "7_7") (pintype "passive"))
      (node (ref "SOCKET_2") (pin "24") (pinfunction "24_24") (pintype "bidirectional"))
    )
    (net (code "185") (name "SERV_PAD_O_TDO_0") (class "Default")
      (node (ref "SERV_JTAG") (pin "5") (pinfunction "5_5") (pintype "passive"))
      (node (ref "SOCKET_2") (pin "19") (pinfunction "19_19") (pintype "bidirectional"))
    )
    (net (code "186") (name "SERV_PAD_RX_IN_0") (class "Default")
      (node (ref "SERV_UART") (pin "1") (pinfunction "1_1") (pintype "passive"))
      (node (ref "SOCKET_2") (pin "35") (pinfunction "35_35") (pintype "bidirectional"))
    )
    (net (code "187") (name "SERV_PAD_TX_OUT_0") (class "Default")
      (node (ref "SERV_UART") (pin "3") (pinfunction "3_3") (pintype "passive"))
      (node (ref "SOCKET_2") (pin "34") (pinfunction "34_34") (pintype "bidirectional"))
    )
    (net (code "188") (name "SERV_PAD_VDD_0") (class "Default")
      (node (ref "C29") (pin "1") (pinfunction "1_1") (pintype "passive"))
      (node (ref "C32") (pin "1") (pinfunction "1_1") (pintype "passive"))
      (node (ref "SERV_POWER") (pin "4") (pinfunction "4_4") (pintype "passive"))
      (node (ref "SOCKET_2") (pin "11") (pinfunction "11_11") (pintype "bidirectional"))
    )
    (net (code "189") (name "SERV_PAD_VDD_RAM_0") (class "Default")
      (node (ref "C30") (pin "1") (pinfunction "1_1") (pintype "passive"))
      (node (ref "C31") (pin "1") (pinfunction "1_1") (pintype "passive"))
      (node (ref "SERV_POWER") (pin "2") (pinfunction "2_2") (pintype "passive"))
      (node (ref "SOCKET_2") (pin "32") (pinfunction "32_32") (pintype "bidirectional"))
    )
    (net (code "190") (name "SERV_SPI_CIPO") (class "Default")
      (node (ref "IC7") (pin "14") (pinfunction "B6_14") (pintype "bidirectional"))
    )
    (net (code "191") (name "SERV_SPI_COPI") (class "Default")
      (node (ref "EPAPER") (pin "6") (pinfunction "6_6") (pintype "passive"))
      (node (ref "IC7") (pin "13") (pinfunction "B7_13") (pintype "bidirectional"))
    )
    (net (code "192") (name "SERV_SPI_CS") (class "Default")
      (node (ref "EPAPER") (pin "4") (pinfunction "4_4") (pintype "passive"))
      (node (ref "IC7") (pin "15") (pinfunction "B5_15") (pintype "bidirectional"))
    )
    (net (code "193") (name "SERV_SPI_SCK") (class "Default")
      (node (ref "EPAPER") (pin "5") (pinfunction "5_5") (pintype "passive"))
      (node (ref "IC7") (pin "12") (pinfunction "B8_12") (pintype "bidirectional"))
    )
    (net (code "194") (name "SERV_UART_RX") (class "Default")
      (node (ref "IC10") (pin "18") (pinfunction "B2_18") (pintype "bidirectional"))
      (node (ref "USB-UART_SERV_1") (pin "2") (pinfunction "2_2") (pintype "passive"))
    )
    (net (code "195") (name "SERV_UART_TX") (class "Default")
      (node (ref "IC10") (pin "17") (pinfunction "B3_17") (pintype "bidirectional"))
      (node (ref "USB-UART_SERV_1") (pin "4") (pinfunction "4_4") (pintype "passive"))
    )
    (net (code "196") (name "SMA_CLK") (class "Default")
      (node (ref "J2") (pin "5") (pinfunction "5_5") (pintype "bidirectional"))
      (node (ref "SERV_CLK") (pin "1") (pinfunction "1_1") (pintype "passive"))
    )
    (net (code "197") (name "SMA_CLK_LEROS") (class "Default")
      (node (ref "J3") (pin "5") (pinfunction "5_5") (pintype "bidirectional"))
      (node (ref "LEROS_CLOCK") (pin "1") (pinfunction "1_1") (pintype "passive"))
    )
    (net (code "198") (name "SPI_CS_0_0") (class "Default")
      (node (ref "SD_CARD") (pin "12") (pinfunction "12_12") (pintype "passive"))
      (node (ref "SOCKET_4") (pin "49") (pinfunction "49_49") (pintype "bidirectional"))
    )
    (net (code "199") (name "SPI_CS_1_0") (class "Default")
      (node (ref "FLASH") (pin "12") (pinfunction "12_12") (pintype "passive"))
      (node (ref "SOCKET_4") (pin "43") (pinfunction "43_43") (pintype "bidirectional"))
    )
    (net (code "200") (name "SPI_DQ_0_0") (class "Default")
      (node (ref "SD_CARD") (pin "10") (pinfunction "10_10") (pintype "passive"))
      (node (ref "SOCKET_4") (pin "48") (pinfunction "48_48") (pintype "bidirectional"))
    )
    (net (code "201") (name "SPI_DQ_0_1") (class "Default")
      (node (ref "SD_CARD") (pin "8") (pinfunction "8_8") (pintype "passive"))
      (node (ref "SOCKET_4") (pin "47") (pinfunction "47_47") (pintype "bidirectional"))
    )
    (net (code "202") (name "SPI_DQ_0_2") (class "Default")
      (node (ref "SOCKET_4") (pin "46") (pinfunction "46_46") (pintype "bidirectional"))
    )
    (net (code "203") (name "SPI_DQ_0_3") (class "Default")
      (node (ref "SOCKET_4") (pin "45") (pinfunction "45_45") (pintype "bidirectional"))
    )
    (net (code "204") (name "SPI_DQ_1_0") (class "Default")
      (node (ref "FLASH") (pin "10") (pinfunction "10_10") (pintype "passive"))
      (node (ref "SOCKET_4") (pin "40") (pinfunction "40_40") (pintype "bidirectional"))
    )
    (net (code "205") (name "SPI_DQ_1_1") (class "Default")
      (node (ref "FLASH") (pin "8") (pinfunction "8_8") (pintype "passive"))
      (node (ref "SOCKET_4") (pin "39") (pinfunction "39_39") (pintype "bidirectional"))
    )
    (net (code "206") (name "SPI_DQ_1_2") (class "Default")
      (node (ref "SOCKET_4") (pin "38") (pinfunction "38_38") (pintype "bidirectional"))
    )
    (net (code "207") (name "SPI_DQ_1_3") (class "Default")
      (node (ref "SOCKET_4") (pin "37") (pinfunction "37_37") (pintype "bidirectional"))
    )
    (net (code "208") (name "SPI_SCK_0") (class "Default")
      (node (ref "SD_CARD") (pin "6") (pinfunction "6_6") (pintype "passive"))
      (node (ref "SOCKET_4") (pin "50") (pinfunction "50_50") (pintype "bidirectional"))
    )
    (net (code "209") (name "SPI_SCK_1") (class "Default")
      (node (ref "FLASH") (pin "6") (pinfunction "6_6") (pintype "passive"))
      (node (ref "SOCKET_4") (pin "44") (pinfunction "44_44") (pintype "bidirectional"))
    )
    (net (code "210") (name "SYS_CLOCK") (class "Default")
      (node (ref "J4") (pin "5") (pinfunction "5_5") (pintype "bidirectional"))
      (node (ref "SOCKET_3") (pin "37") (pinfunction "37_37") (pintype "bidirectional"))
      (node (ref "SYS_CLK") (pin "2") (pinfunction "2_2") (pintype "passive"))
    )
    (net (code "211") (name "SYS_CLOCK_GPIO") (class "Default")
      (node (ref "ROCKET_FPGA") (pin "25") (pinfunction "25_25") (pintype "passive"))
      (node (ref "SYS_CLK") (pin "1") (pinfunction "1_1") (pintype "passive"))
    )
    (net (code "212") (name "SYS_RSTN") (class "Default")
      (node (ref "ROCKET_FPGA") (pin "26") (pinfunction "26_26") (pintype "passive"))
      (node (ref "SOCKET_3") (pin "38") (pinfunction "38_38") (pintype "bidirectional"))
    )
    (net (code "213") (name "UART_RXD_0") (class "Default")
      (node (ref "SOCKET_4") (pin "35") (pinfunction "35_35") (pintype "bidirectional"))
      (node (ref "USB-UART_1") (pin "2") (pinfunction "2_2") (pintype "passive"))
    )
    (net (code "214") (name "UART_TXD_0") (class "Default")
      (node (ref "SOCKET_4") (pin "36") (pinfunction "36_36") (pintype "bidirectional"))
      (node (ref "USB-UART_1") (pin "4") (pinfunction "4_4") (pintype "passive"))
    )
    (net (code "215") (name "VDD_1.8_1") (class "Default")
      (node (ref "C10") (pin "1") (pinfunction "1_1") (pintype "passive"))
      (node (ref "IC5") (pin "2") (pinfunction "VOUT_1_2") (pintype "bidirectional"))
      (node (ref "IC5") (pin "4") (pinfunction "VOUT_2_4") (pintype "bidirectional"))
      (node (ref "POWER_AES") (pin "1") (pinfunction "1_1") (pintype "passive"))
      (node (ref "POWER_LEROS") (pin "1") (pinfunction "1_1") (pintype "passive"))
      (node (ref "ROCKET_POWER") (pin "1") (pinfunction "1_1") (pintype "passive"))
      (node (ref "SERV_POWER") (pin "1") (pinfunction "1_1") (pintype "passive"))
    )
    (net (code "216") (name "VDD_1.8_2") (class "Default")
      (node (ref "C8") (pin "1") (pinfunction "1_1") (pintype "passive"))
      (node (ref "IC1") (pin "2") (pinfunction "VOUT_1_2") (pintype "bidirectional"))
      (node (ref "IC1") (pin "4") (pinfunction "VOUT_2_4") (pintype "bidirectional"))
      (node (ref "POWER_DLDO") (pin "1") (pinfunction "1_1") (pintype "passive"))
      (node (ref "POWER_LEROS") (pin "3") (pinfunction "3_3") (pintype "passive"))
      (node (ref "ROCKET_POWER") (pin "3") (pinfunction "3_3") (pintype "passive"))
      (node (ref "SERV_POWER") (pin "3") (pinfunction "3_3") (pintype "passive"))
    )
    (net (code "217") (name "VDD_1.8_3") (class "Default")
      (node (ref "C20") (pin "1") (pinfunction "1_1") (pintype "passive"))
      (node (ref "IC4") (pin "2") (pinfunction "VOUT_1_2") (pintype "bidirectional"))
      (node (ref "IC4") (pin "4") (pinfunction "VOUT_2_4") (pintype "bidirectional"))
      (node (ref "POWER_LEROS") (pin "5") (pinfunction "5_5") (pintype "passive"))
    )
    (net (code "218") (name "VDD_1.8_CORE") (class "Default")
      (node (ref "C34") (pin "1") (pinfunction "1_1") (pintype "passive"))
      (node (ref "C35") (pin "1") (pinfunction "1_1") (pintype "passive"))
      (node (ref "ROCKET_POWER") (pin "2") (pinfunction "2_2") (pintype "passive"))
      (node (ref "SOCKET_1") (pin "11") (pinfunction "11_11") (pintype "bidirectional"))
      (node (ref "SOCKET_1") (pin "32") (pinfunction "32_32") (pintype "bidirectional"))
      (node (ref "SOCKET_3") (pin "32") (pinfunction "32_32") (pintype "bidirectional"))
      (node (ref "SOCKET_3") (pin "52") (pinfunction "52_52") (pintype "bidirectional"))
      (node (ref "SOCKET_4") (pin "11") (pinfunction "11_11") (pintype "bidirectional"))
      (node (ref "SOCKET_4") (pin "32") (pinfunction "32_32") (pintype "bidirectional"))
      (node (ref "SOCKET_4") (pin "52") (pinfunction "52_52") (pintype "bidirectional"))
    )
    (net (code "219") (name "VDD_1.8_IO") (class "Default")
      (node (ref "C15") (pin "1") (pinfunction "1_1") (pintype "passive"))
      (node (ref "C17") (pin "1") (pinfunction "1_1") (pintype "passive"))
      (node (ref "C33") (pin "1") (pinfunction "1_1") (pintype "passive"))
      (node (ref "C36") (pin "1") (pinfunction "1_1") (pintype "passive"))
      (node (ref "IC10") (pin "10") (pinfunction "OE_10") (pintype "bidirectional"))
      (node (ref "IC10") (pin "2") (pinfunction "VCCA_2") (pintype "bidirectional"))
      (node (ref "IC7") (pin "10") (pinfunction "OE_10") (pintype "bidirectional"))
      (node (ref "IC7") (pin "2") (pinfunction "VCCA_2") (pintype "bidirectional"))
      (node (ref "ROCKET_POWER") (pin "4") (pinfunction "4_4") (pintype "passive"))
      (node (ref "SOCKET_2") (pin "1") (pinfunction "1_1") (pintype "bidirectional"))
      (node (ref "SOCKET_2") (pin "21") (pinfunction "21_21") (pintype "bidirectional"))
      (node (ref "SOCKET_2") (pin "41") (pinfunction "41_41") (pintype "bidirectional"))
      (node (ref "SOCKET_3") (pin "1") (pinfunction "1_1") (pintype "bidirectional"))
      (node (ref "SOCKET_3") (pin "21") (pinfunction "21_21") (pintype "bidirectional"))
      (node (ref "SOCKET_3") (pin "42") (pinfunction "42_42") (pintype "bidirectional"))
    )
    (net (code "220") (name "VDD_3V3") (class "Default")
      (node (ref "C16") (pin "1") (pinfunction "1_1") (pintype "passive"))
      (node (ref "C18") (pin "1") (pinfunction "1_1") (pintype "passive"))
      (node (ref "C19") (pin "1") (pinfunction "1_1") (pintype "passive"))
      (node (ref "C21") (pin "1") (pinfunction "1_1") (pintype "passive"))
      (node (ref "C22") (pin "1") (pinfunction "1_1") (pintype "passive"))
      (node (ref "C37") (pin "1") (pinfunction "1_1") (pintype "passive"))
      (node (ref "C38") (pin "1") (pinfunction "1_1") (pintype "passive"))
      (node (ref "C39") (pin "1") (pinfunction "1_1") (pintype "passive"))
      (node (ref "C40") (pin "1") (pinfunction "1_1") (pintype "passive"))
      (node (ref "C41") (pin "1") (pinfunction "1_1") (pintype "passive"))
      (node (ref "C42") (pin "1") (pinfunction "1_1") (pintype "passive"))
      (node (ref "C7") (pin "1") (pinfunction "1_1") (pintype "passive"))
      (node (ref "C9") (pin "1") (pinfunction "1_1") (pintype "passive"))
      (node (ref "EPAPER") (pin "8") (pinfunction "8_8") (pintype "passive"))
      (node (ref "FLASH") (pin "1") (pinfunction "1_1") (pintype "passive"))
      (node (ref "FLASH") (pin "2") (pinfunction "2_2") (pintype "passive"))
      (node (ref "FLASH_SERV") (pin "1") (pinfunction "1_1") (pintype "passive"))
      (node (ref "FLASH_SERV") (pin "2") (pinfunction "2_2") (pintype "passive"))
      (node (ref "IC1") (pin "3") (pinfunction "VIN_3") (pintype "bidirectional"))
      (node (ref "IC10") (pin "19") (pinfunction "VCCB_19") (pintype "bidirectional"))
      (node (ref "IC3") (pin "1") (pinfunction "VDD_1_1") (pintype "bidirectional"))
      (node (ref "IC3") (pin "14") (pinfunction "VDD_2_14") (pintype "bidirectional"))
      (node (ref "IC3") (pin "27") (pinfunction "VDD_3_27") (pintype "bidirectional"))
      (node (ref "IC3") (pin "3") (pinfunction "VDDQ_1_3") (pintype "bidirectional"))
      (node (ref "IC3") (pin "43") (pinfunction "VDDQ_3_43") (pintype "bidirectional"))
      (node (ref "IC3") (pin "49") (pinfunction "VDDQ_4_49") (pintype "bidirectional"))
      (node (ref "IC3") (pin "9") (pinfunction "VDDQ_2_9") (pintype "bidirectional"))
      (node (ref "IC4") (pin "3") (pinfunction "VIN_3") (pintype "bidirectional"))
      (node (ref "IC5") (pin "3") (pinfunction "VIN_3") (pintype "bidirectional"))
      (node (ref "IC7") (pin "19") (pinfunction "VCCB_19") (pintype "bidirectional"))
      (node (ref "JTAG_ROCKET") (pin "1") (pinfunction "1_1") (pintype "passive"))
      (node (ref "JTAG_ROCKET") (pin "2") (pinfunction "2_2") (pintype "passive"))
      (node (ref "JTAG_SERV") (pin "1") (pinfunction "1_1") (pintype "passive"))
      (node (ref "JTAG_SERV") (pin "2") (pinfunction "2_2") (pintype "passive"))
      (node (ref "POWER_3.3V") (pin "6") (pinfunction "6_6") (pintype "passive"))
      (node (ref "R1") (pin "2") (pinfunction "2_2") (pintype "passive"))
      (node (ref "R11") (pin "2") (pinfunction "2_2") (pintype "passive"))
      (node (ref "R2") (pin "2") (pinfunction "2_2") (pintype "passive"))
      (node (ref "S1") (pin "1") (pinfunction "ON_1_1") (pintype "bidirectional"))
      (node (ref "S2") (pin "1") (pinfunction "ON_1_1") (pintype "bidirectional"))
      (node (ref "S3") (pin "1") (pinfunction "ON_1_1") (pintype "bidirectional"))
      (node (ref "SD_CARD") (pin "1") (pinfunction "1_1") (pintype "passive"))
      (node (ref "SD_CARD") (pin "2") (pinfunction "2_2") (pintype "passive"))
    )
    (net (code "221") (name "VDD_3V3_ALL") (class "Default")
      (node (ref "3.3V_MUX") (pin "2") (pinfunction "2_2") (pintype "passive"))
      (node (ref "POWER_3.3V") (pin "1") (pinfunction "1_1") (pintype "passive"))
      (node (ref "POWER_3.3V") (pin "3") (pinfunction "3_3") (pintype "passive"))
      (node (ref "POWER_3.3V") (pin "5") (pinfunction "5_5") (pintype "passive"))
    )
    (net (code "222") (name "VDD_3V3_GPIO") (class "Default")
      (node (ref "3.3V_MUX") (pin "3") (pinfunction "3_3") (pintype "passive"))
      (node (ref "FPGA_LEROS") (pin "1") (pinfunction "1_1") (pintype "passive"))
      (node (ref "ROCKET_FPGA") (pin "29") (pinfunction "29_29") (pintype "passive"))
    )
    (net (code "223") (name "VDD_3V3_IO") (class "Default")
      (node (ref "POWER_3.3V") (pin "4") (pinfunction "4_4") (pintype "passive"))
      (node (ref "SOCKET_1") (pin "1") (pinfunction "1_1") (pintype "bidirectional"))
      (node (ref "SOCKET_1") (pin "21") (pinfunction "21_21") (pintype "bidirectional"))
      (node (ref "SOCKET_1") (pin "42") (pinfunction "42_42") (pintype "bidirectional"))
      (node (ref "SOCKET_4") (pin "1") (pinfunction "1_1") (pintype "bidirectional"))
      (node (ref "SOCKET_4") (pin "21") (pinfunction "21_21") (pintype "bidirectional"))
      (node (ref "SOCKET_4") (pin "42") (pinfunction "42_42") (pintype "bidirectional"))
    )
    (net (code "224") (name "VDD_3V3_UART") (class "Default")
      (node (ref "3.3V_MUX") (pin "1") (pinfunction "1_1") (pintype "passive"))
      (node (ref "USB-UART_SERV_1") (pin "3") (pinfunction "3_3") (pintype "passive"))
    )
    (net (code "225") (name "VDD_5V") (class "Default")
      (node (ref "USB-UART_SERV_2") (pin "2") (pinfunction "2_2") (pintype "passive"))
    )
    (net (code "226") (name "VDD_5V_USB") (class "Default")
      (node (ref "USB-UART_2") (pin "2") (pinfunction "2_2") (pintype "passive"))
    )
    (net (code "227") (name "VDD_AES") (class "Default")
      (node (ref "C26") (pin "1") (pinfunction "1_1") (pintype "passive"))
      (node (ref "C27") (pin "1") (pinfunction "1_1") (pintype "passive"))
      (node (ref "POWER_AES") (pin "2") (pinfunction "2_2") (pintype "passive"))
      (node (ref "SOCKET_3") (pin "48") (pinfunction "48_48") (pintype "bidirectional"))
    )
    (net (code "228") (name "unconnected-(FLASH-Pad5)") (class "Default")
      (node (ref "FLASH") (pin "5") (pinfunction "5_5") (pintype "passive"))
    )
    (net (code "229") (name "unconnected-(FLASH-Pad7)") (class "Default")
      (node (ref "FLASH") (pin "7") (pinfunction "7_7") (pintype "passive"))
    )
    (net (code "230") (name "unconnected-(FLASH-Pad9)") (class "Default")
      (node (ref "FLASH") (pin "9") (pinfunction "9_9") (pintype "passive"))
    )
    (net (code "231") (name "unconnected-(FLASH-Pad11)") (class "Default")
      (node (ref "FLASH") (pin "11") (pinfunction "11_11") (pintype "passive"))
    )
    (net (code "232") (name "unconnected-(FLASH_SERV-Pad5)") (class "Default")
      (node (ref "FLASH_SERV") (pin "5") (pinfunction "5_5") (pintype "passive"))
    )
    (net (code "233") (name "unconnected-(FLASH_SERV-Pad7)") (class "Default")
      (node (ref "FLASH_SERV") (pin "7") (pinfunction "7_7") (pintype "passive"))
    )
    (net (code "234") (name "unconnected-(FLASH_SERV-Pad9)") (class "Default")
      (node (ref "FLASH_SERV") (pin "9") (pinfunction "9_9") (pintype "passive"))
    )
    (net (code "235") (name "unconnected-(FLASH_SERV-Pad11)") (class "Default")
      (node (ref "FLASH_SERV") (pin "11") (pinfunction "11_11") (pintype "passive"))
    )
    (net (code "236") (name "unconnected-(IC3-NC-Pad40)") (class "Default")
      (node (ref "IC3") (pin "40") (pinfunction "NC_40") (pintype "no_connect"))
    )
    (net (code "237") (name "unconnected-(IC10-A1-Pad1)") (class "Default")
      (node (ref "IC10") (pin "1") (pinfunction "A1_1") (pintype "bidirectional"))
    )
    (net (code "238") (name "unconnected-(IC10-B1-Pad20)") (class "Default")
      (node (ref "IC10") (pin "20") (pinfunction "B1_20") (pintype "bidirectional"))
    )
    (net (code "239") (name "unconnected-(JTAG_ROCKET-Pad11)") (class "Default")
      (node (ref "JTAG_ROCKET") (pin "11") (pinfunction "11_11") (pintype "passive"))
    )
    (net (code "240") (name "unconnected-(JTAG_ROCKET-Pad15)") (class "Default")
      (node (ref "JTAG_ROCKET") (pin "15") (pinfunction "15_15") (pintype "passive"))
    )
    (net (code "241") (name "unconnected-(JTAG_ROCKET-Pad17)") (class "Default")
      (node (ref "JTAG_ROCKET") (pin "17") (pinfunction "17_17") (pintype "passive"))
    )
    (net (code "242") (name "unconnected-(JTAG_ROCKET-Pad19)") (class "Default")
      (node (ref "JTAG_ROCKET") (pin "19") (pinfunction "19_19") (pintype "passive"))
    )
    (net (code "243") (name "unconnected-(JTAG_SERV-Pad11)") (class "Default")
      (node (ref "JTAG_SERV") (pin "11") (pinfunction "11_11") (pintype "passive"))
    )
    (net (code "244") (name "unconnected-(JTAG_SERV-Pad15)") (class "Default")
      (node (ref "JTAG_SERV") (pin "15") (pinfunction "15_15") (pintype "passive"))
    )
    (net (code "245") (name "unconnected-(JTAG_SERV-Pad17)") (class "Default")
      (node (ref "JTAG_SERV") (pin "17") (pinfunction "17_17") (pintype "passive"))
    )
    (net (code "246") (name "unconnected-(JTAG_SERV-Pad19)") (class "Default")
      (node (ref "JTAG_SERV") (pin "19") (pinfunction "19_19") (pintype "passive"))
    )
    (net (code "247") (name "unconnected-(ROCKET_FPGA-Pad1)") (class "Default")
      (node (ref "ROCKET_FPGA") (pin "1") (pinfunction "1_1") (pintype "passive"))
    )
    (net (code "248") (name "unconnected-(ROCKET_FPGA-Pad3)") (class "Default")
      (node (ref "ROCKET_FPGA") (pin "3") (pinfunction "3_3") (pintype "passive"))
    )
    (net (code "249") (name "unconnected-(ROCKET_FPGA-Pad11)") (class "Default")
      (node (ref "ROCKET_FPGA") (pin "11") (pinfunction "11_11") (pintype "passive"))
    )
    (net (code "250") (name "unconnected-(SD_CARD-Pad5)") (class "Default")
      (node (ref "SD_CARD") (pin "5") (pinfunction "5_5") (pintype "passive"))
    )
    (net (code "251") (name "unconnected-(SD_CARD-Pad7)") (class "Default")
      (node (ref "SD_CARD") (pin "7") (pinfunction "7_7") (pintype "passive"))
    )
    (net (code "252") (name "unconnected-(SD_CARD-Pad9)") (class "Default")
      (node (ref "SD_CARD") (pin "9") (pinfunction "9_9") (pintype "passive"))
    )
    (net (code "253") (name "unconnected-(SD_CARD-Pad11)") (class "Default")
      (node (ref "SD_CARD") (pin "11") (pinfunction "11_11") (pintype "passive"))
    )
    (net (code "254") (name "unconnected-(SOCKET_3-Pad47)") (class "Default")
      (node (ref "SOCKET_3") (pin "47") (pinfunction "47_47") (pintype "bidirectional"))
    )
    (net (code "255") (name "unconnected-(USB-UART_1-Pad3)") (class "Default")
      (node (ref "USB-UART_1") (pin "3") (pinfunction "3_3") (pintype "passive"))
    )
    (net (code "256") (name "unconnected-(USB-UART_2-Pad1)") (class "Default")
      (node (ref "USB-UART_2") (pin "1") (pinfunction "1_1") (pintype "passive"))
    )
    (net (code "257") (name "unconnected-(USB-UART_2-Pad3)") (class "Default")
      (node (ref "USB-UART_2") (pin "3") (pinfunction "3_3") (pintype "passive"))
    )
    (net (code "258") (name "unconnected-(USB-UART_2-Pad4)") (class "Default")
      (node (ref "USB-UART_2") (pin "4") (pinfunction "4_4") (pintype "passive"))
    )
    (net (code "259") (name "unconnected-(USB-UART_SERV_2-Pad1)") (class "Default")
      (node (ref "USB-UART_SERV_2") (pin "1") (pinfunction "1_1") (pintype "passive"))
    )
    (net (code "260") (name "unconnected-(USB-UART_SERV_2-Pad3)") (class "Default")
      (node (ref "USB-UART_SERV_2") (pin "3") (pinfunction "3_3") (pintype "passive"))
    )
    (net (code "261") (name "unconnected-(USB-UART_SERV_2-Pad4)") (class "Default")
      (node (ref "USB-UART_SERV_2") (pin "4") (pinfunction "4_4") (pintype "passive"))
    )
  )
)
